# ProPrj_EIS-HW-V01_test_2026-05-23.net
KiCad netlist of a schematic drawn in EasyEDA Pro
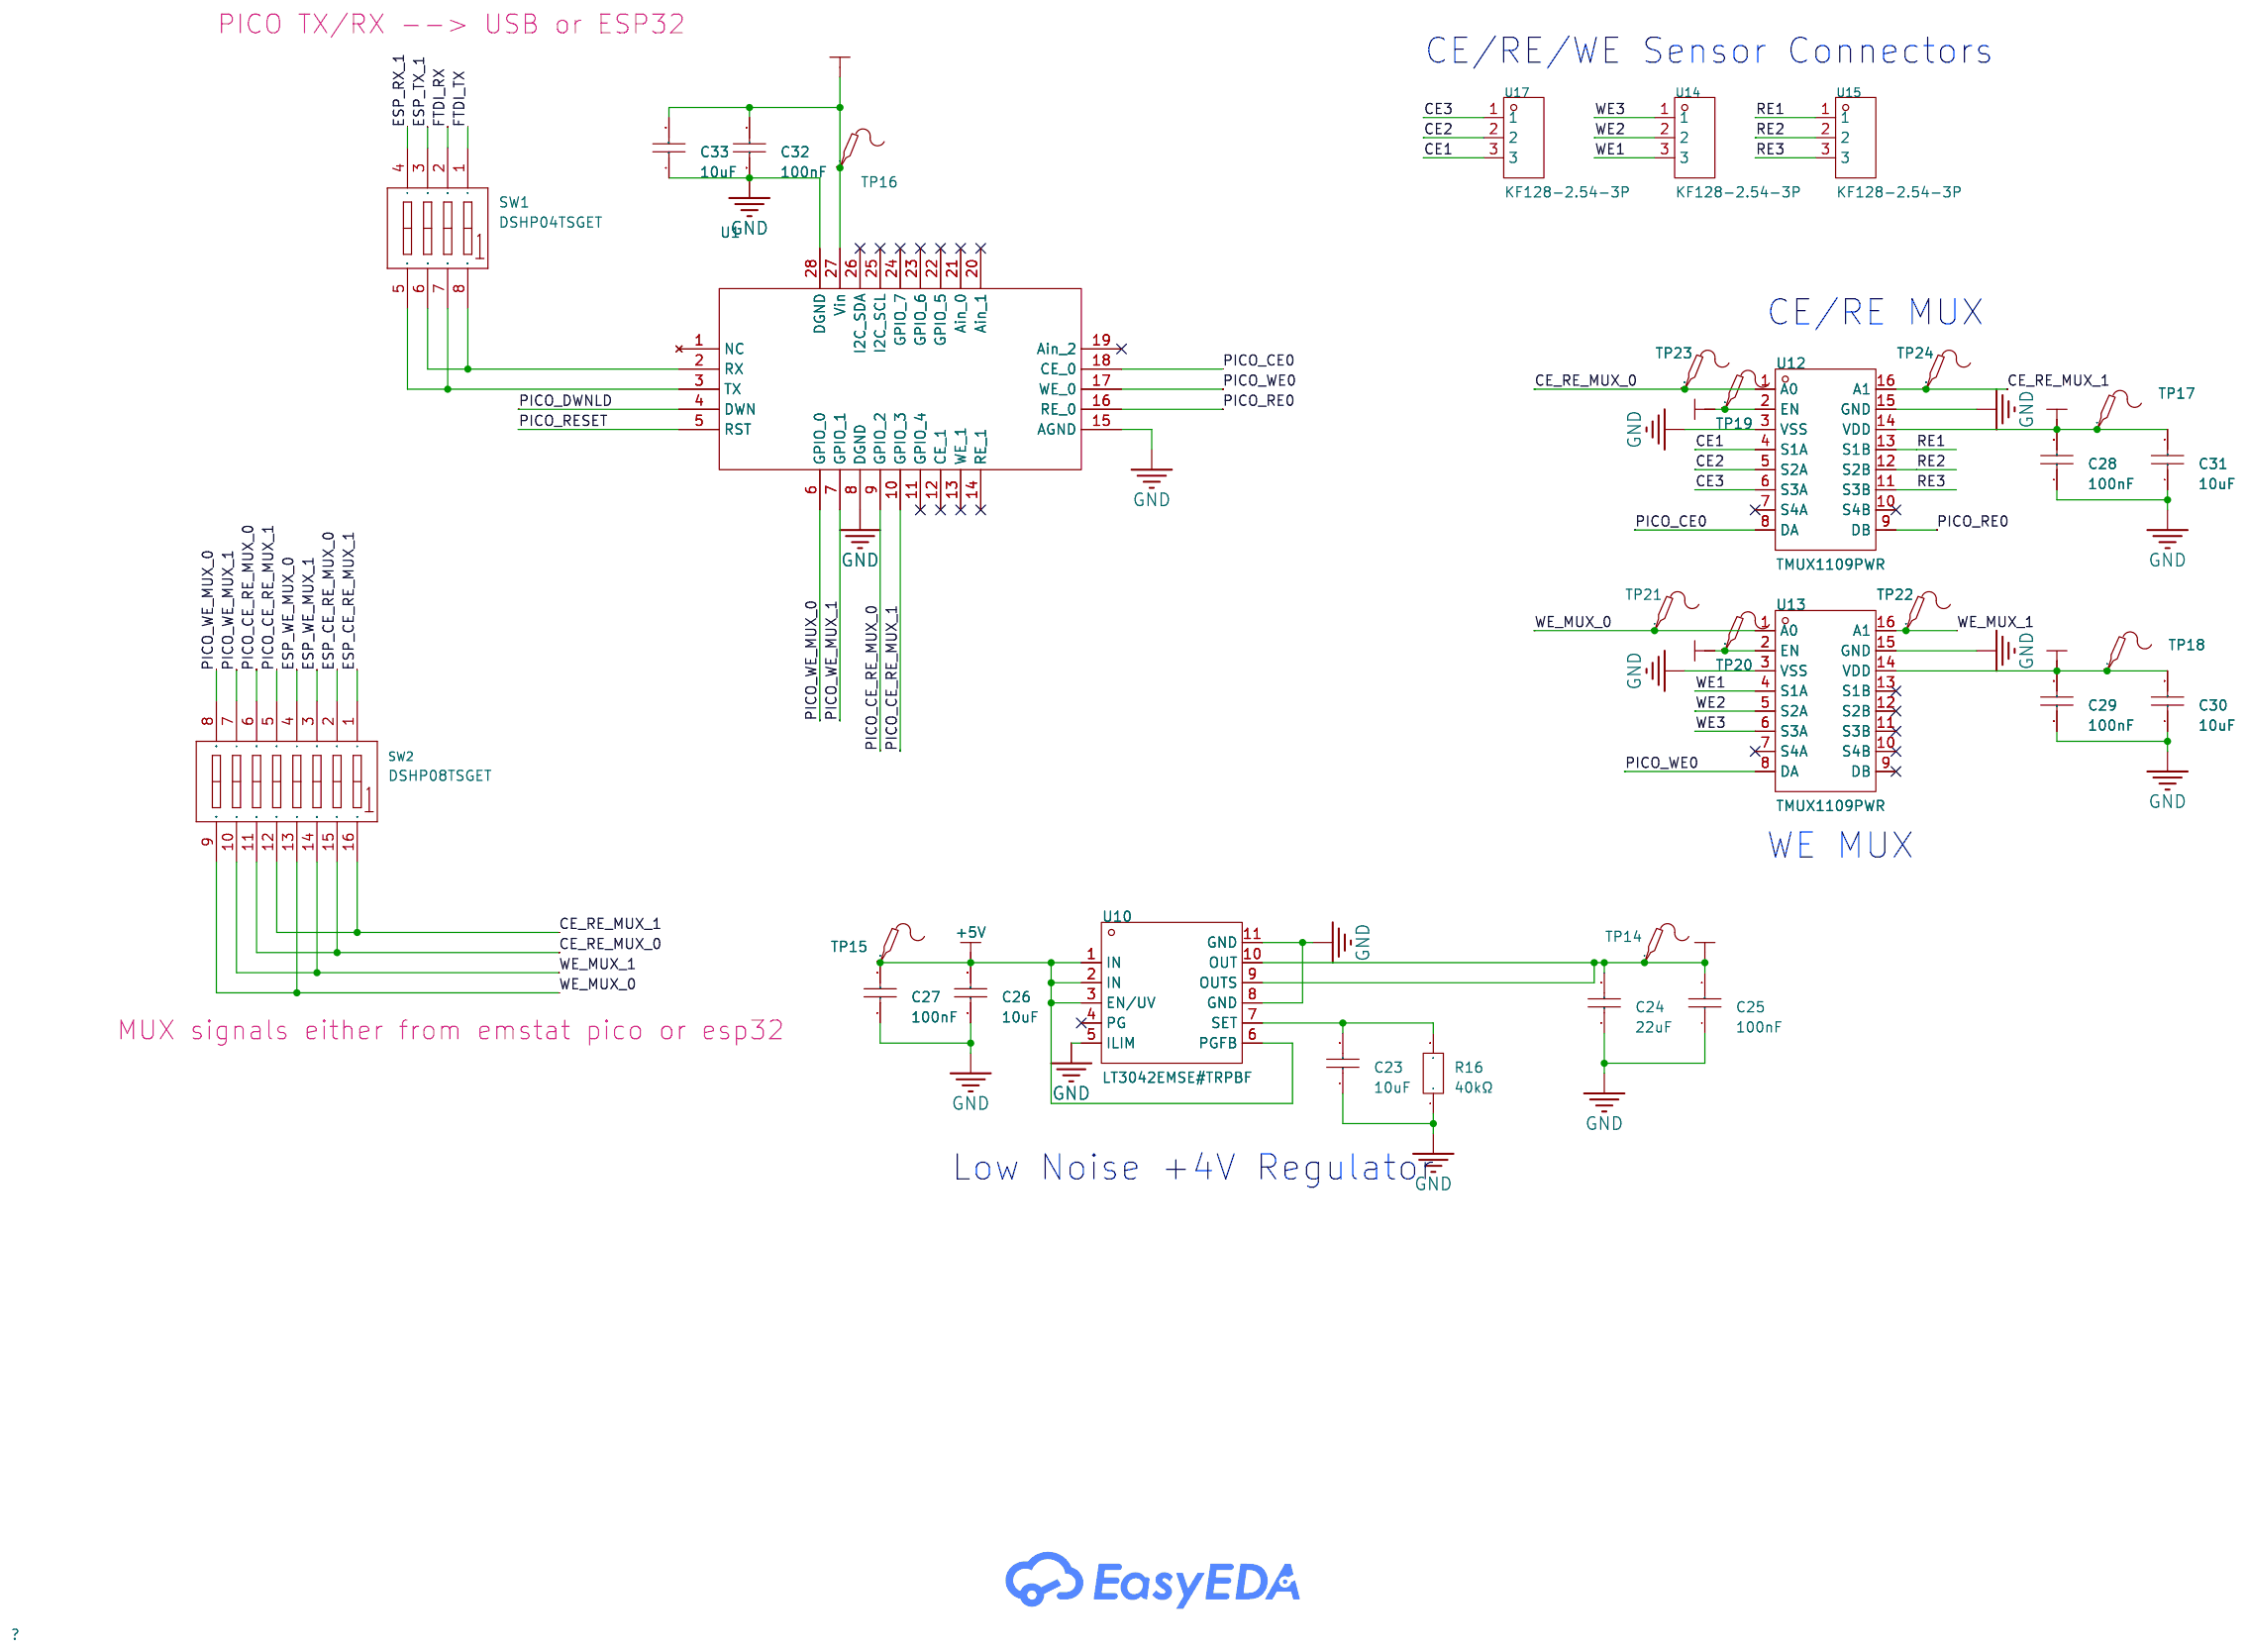
[diagram p0: P1]
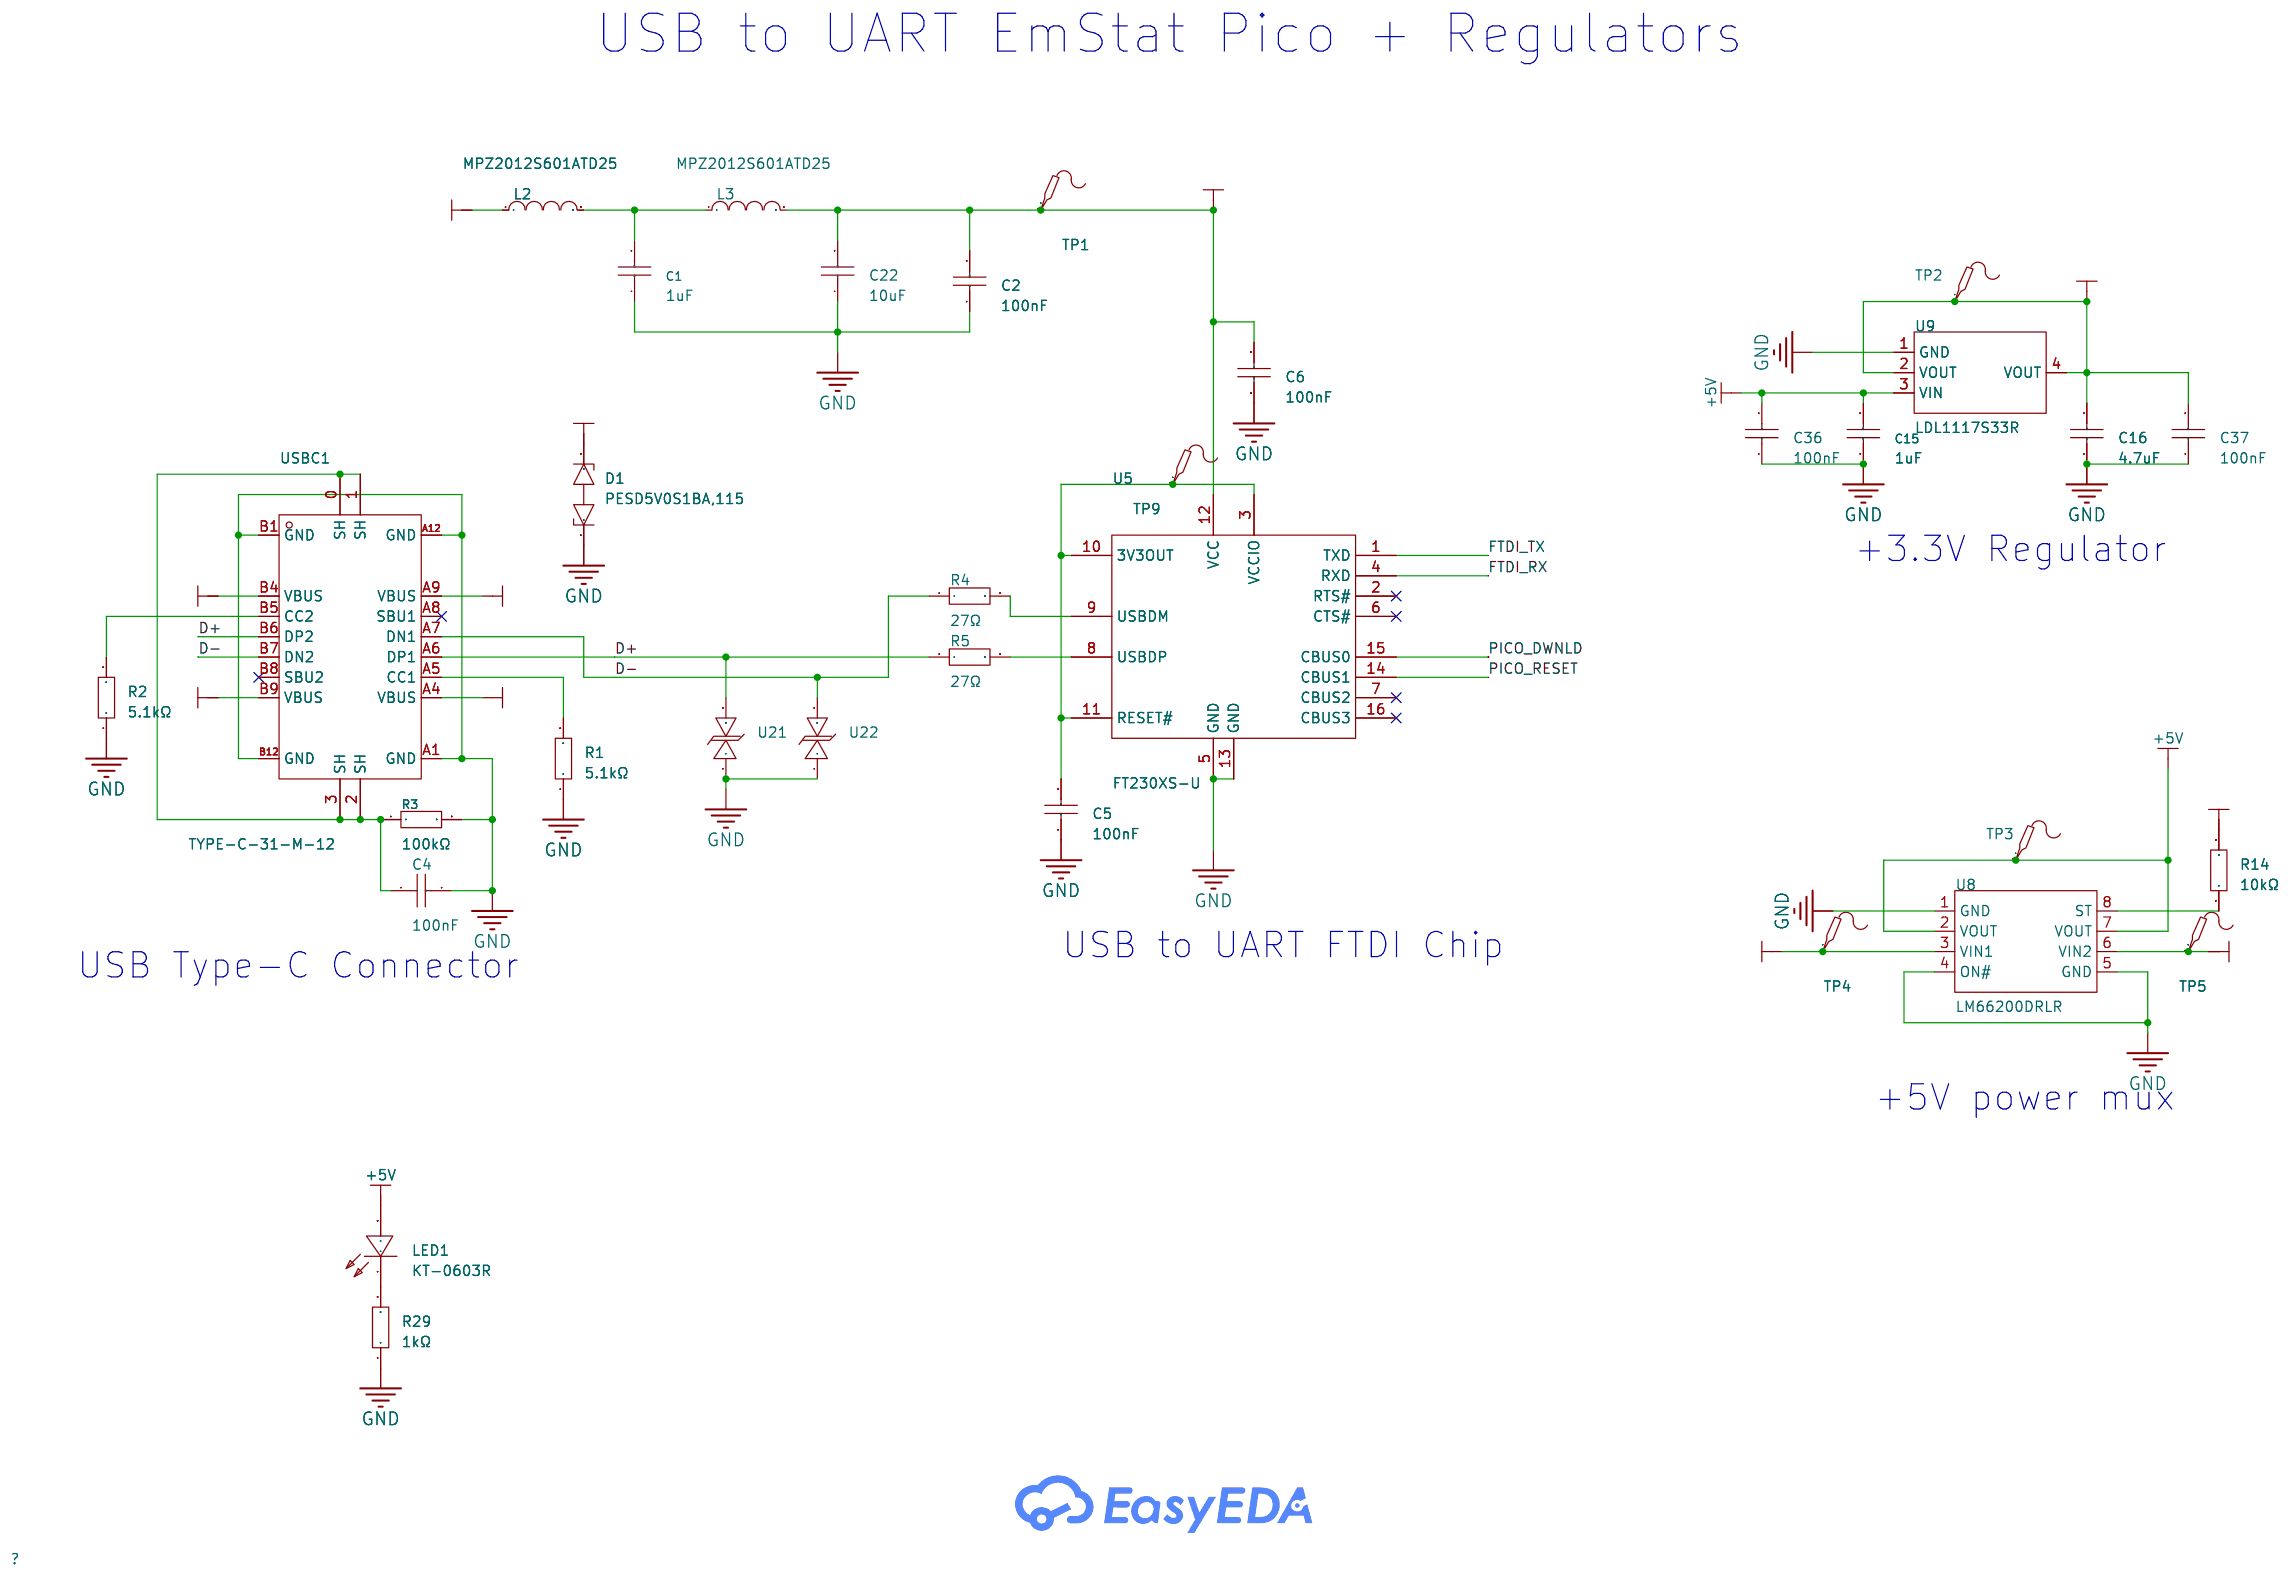
[diagram p1: P2]
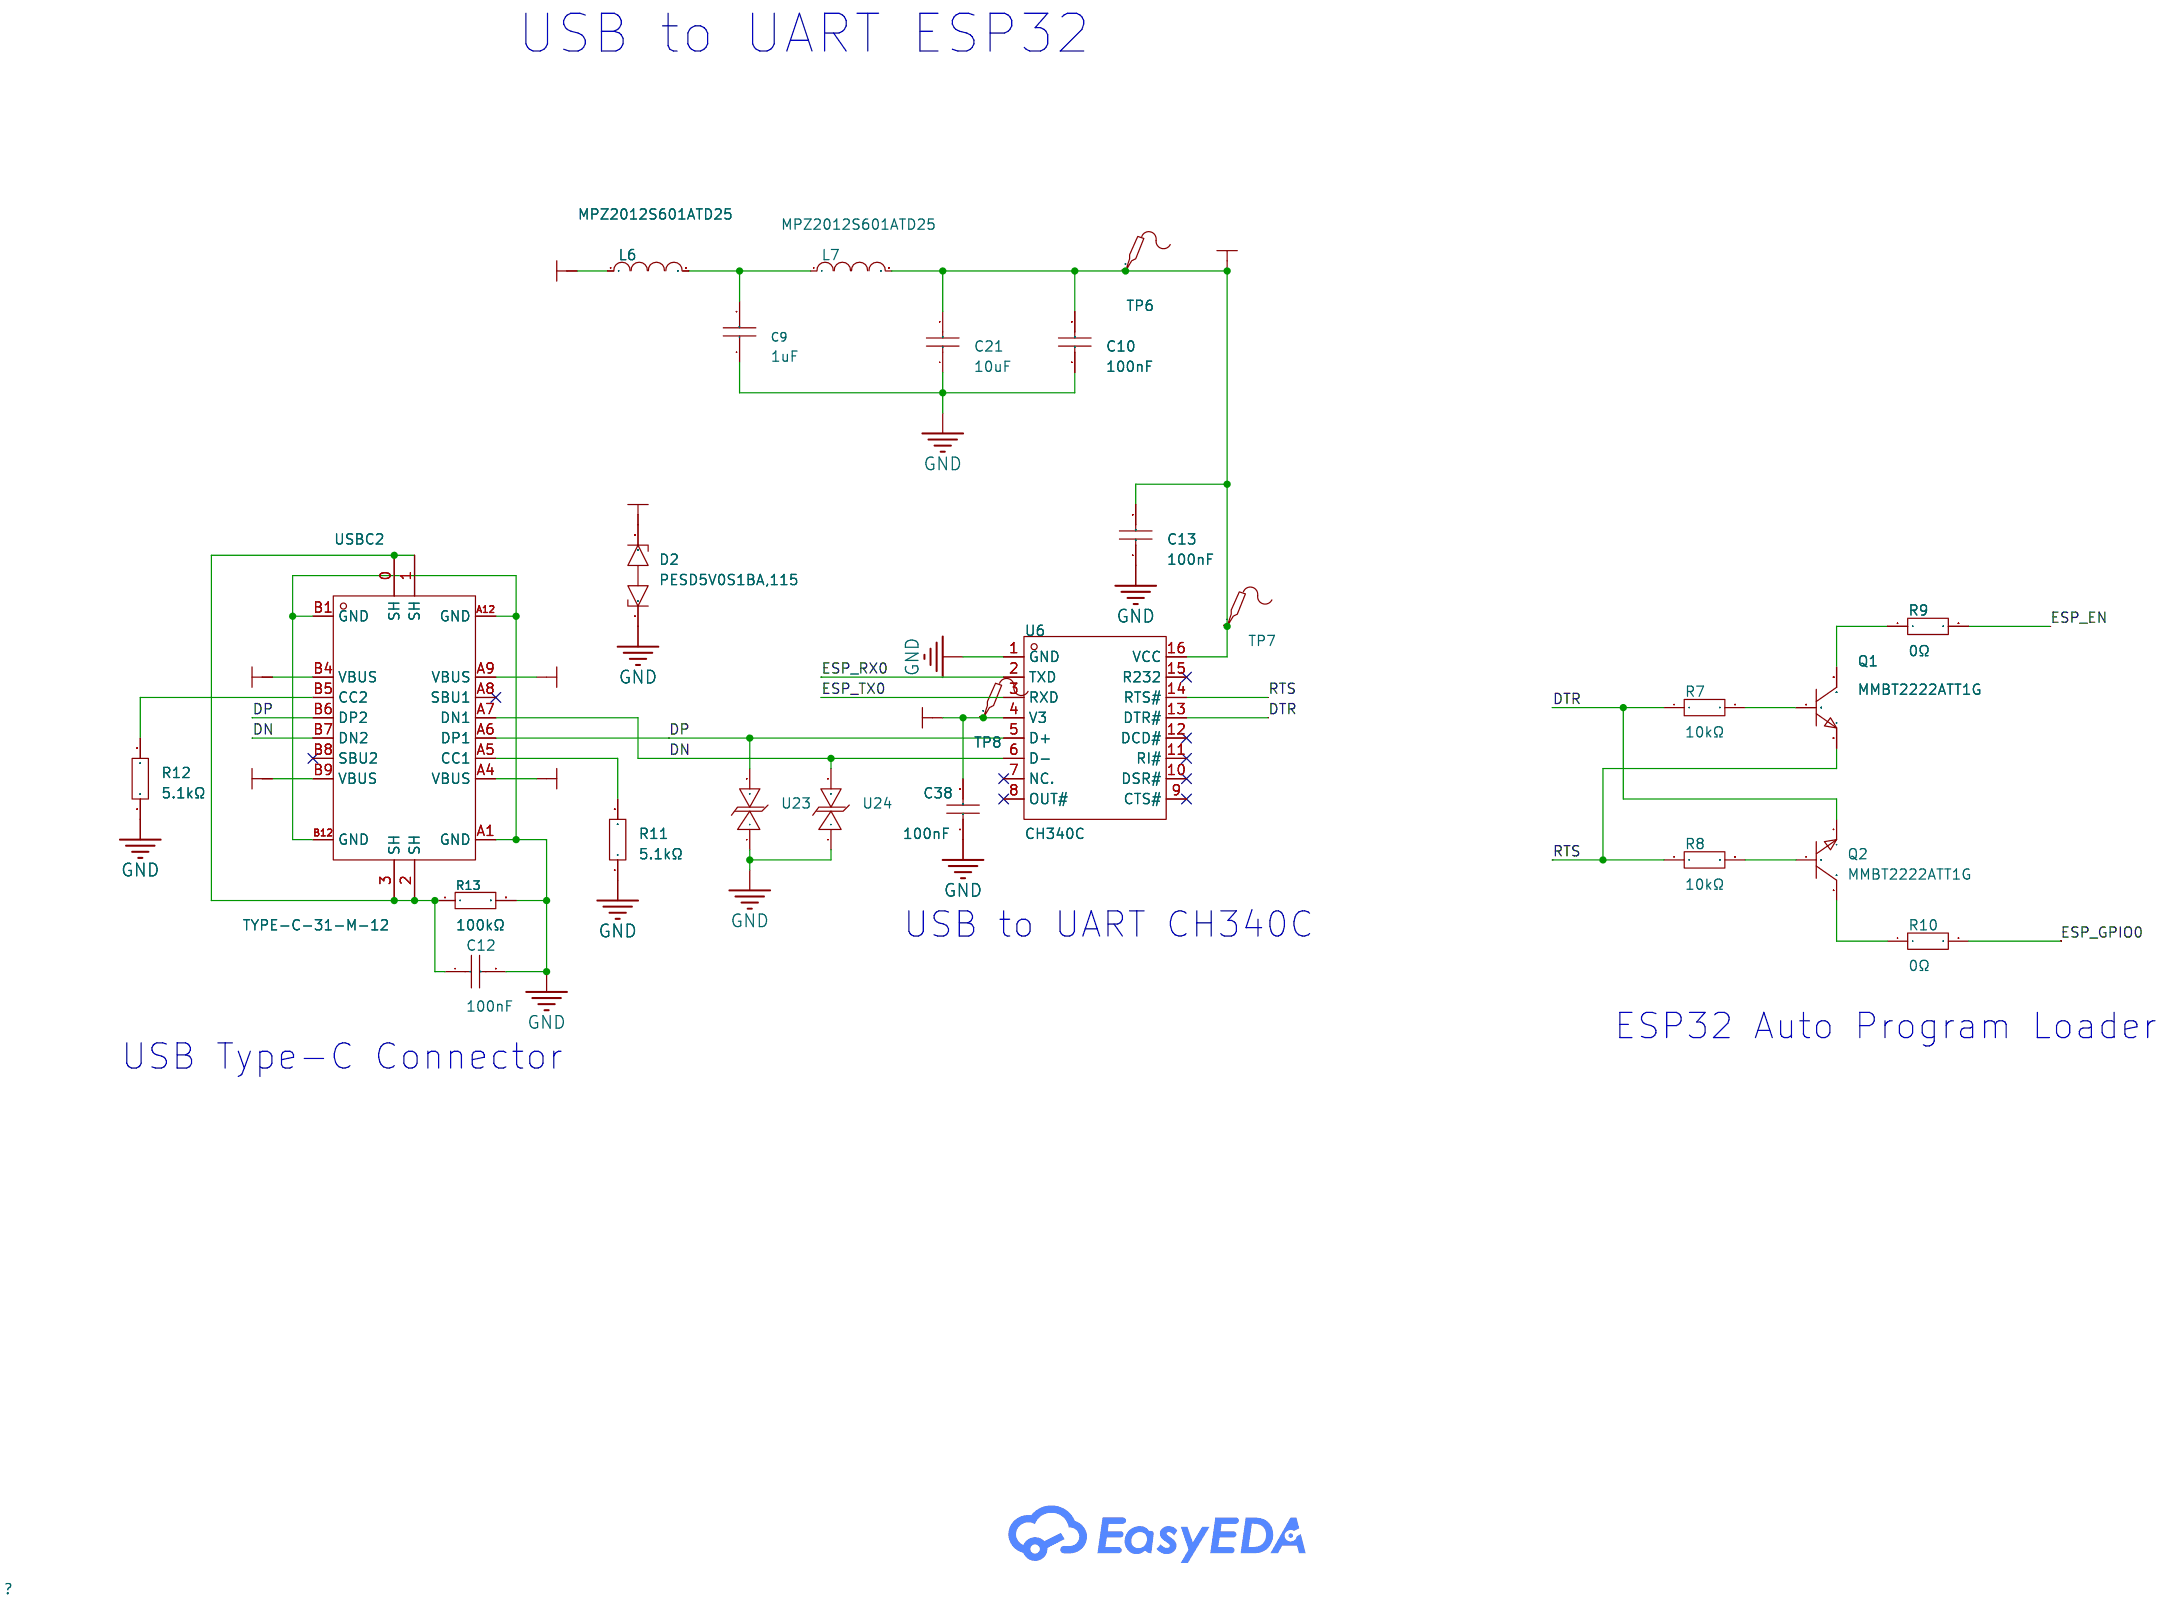
[diagram p2: P3]
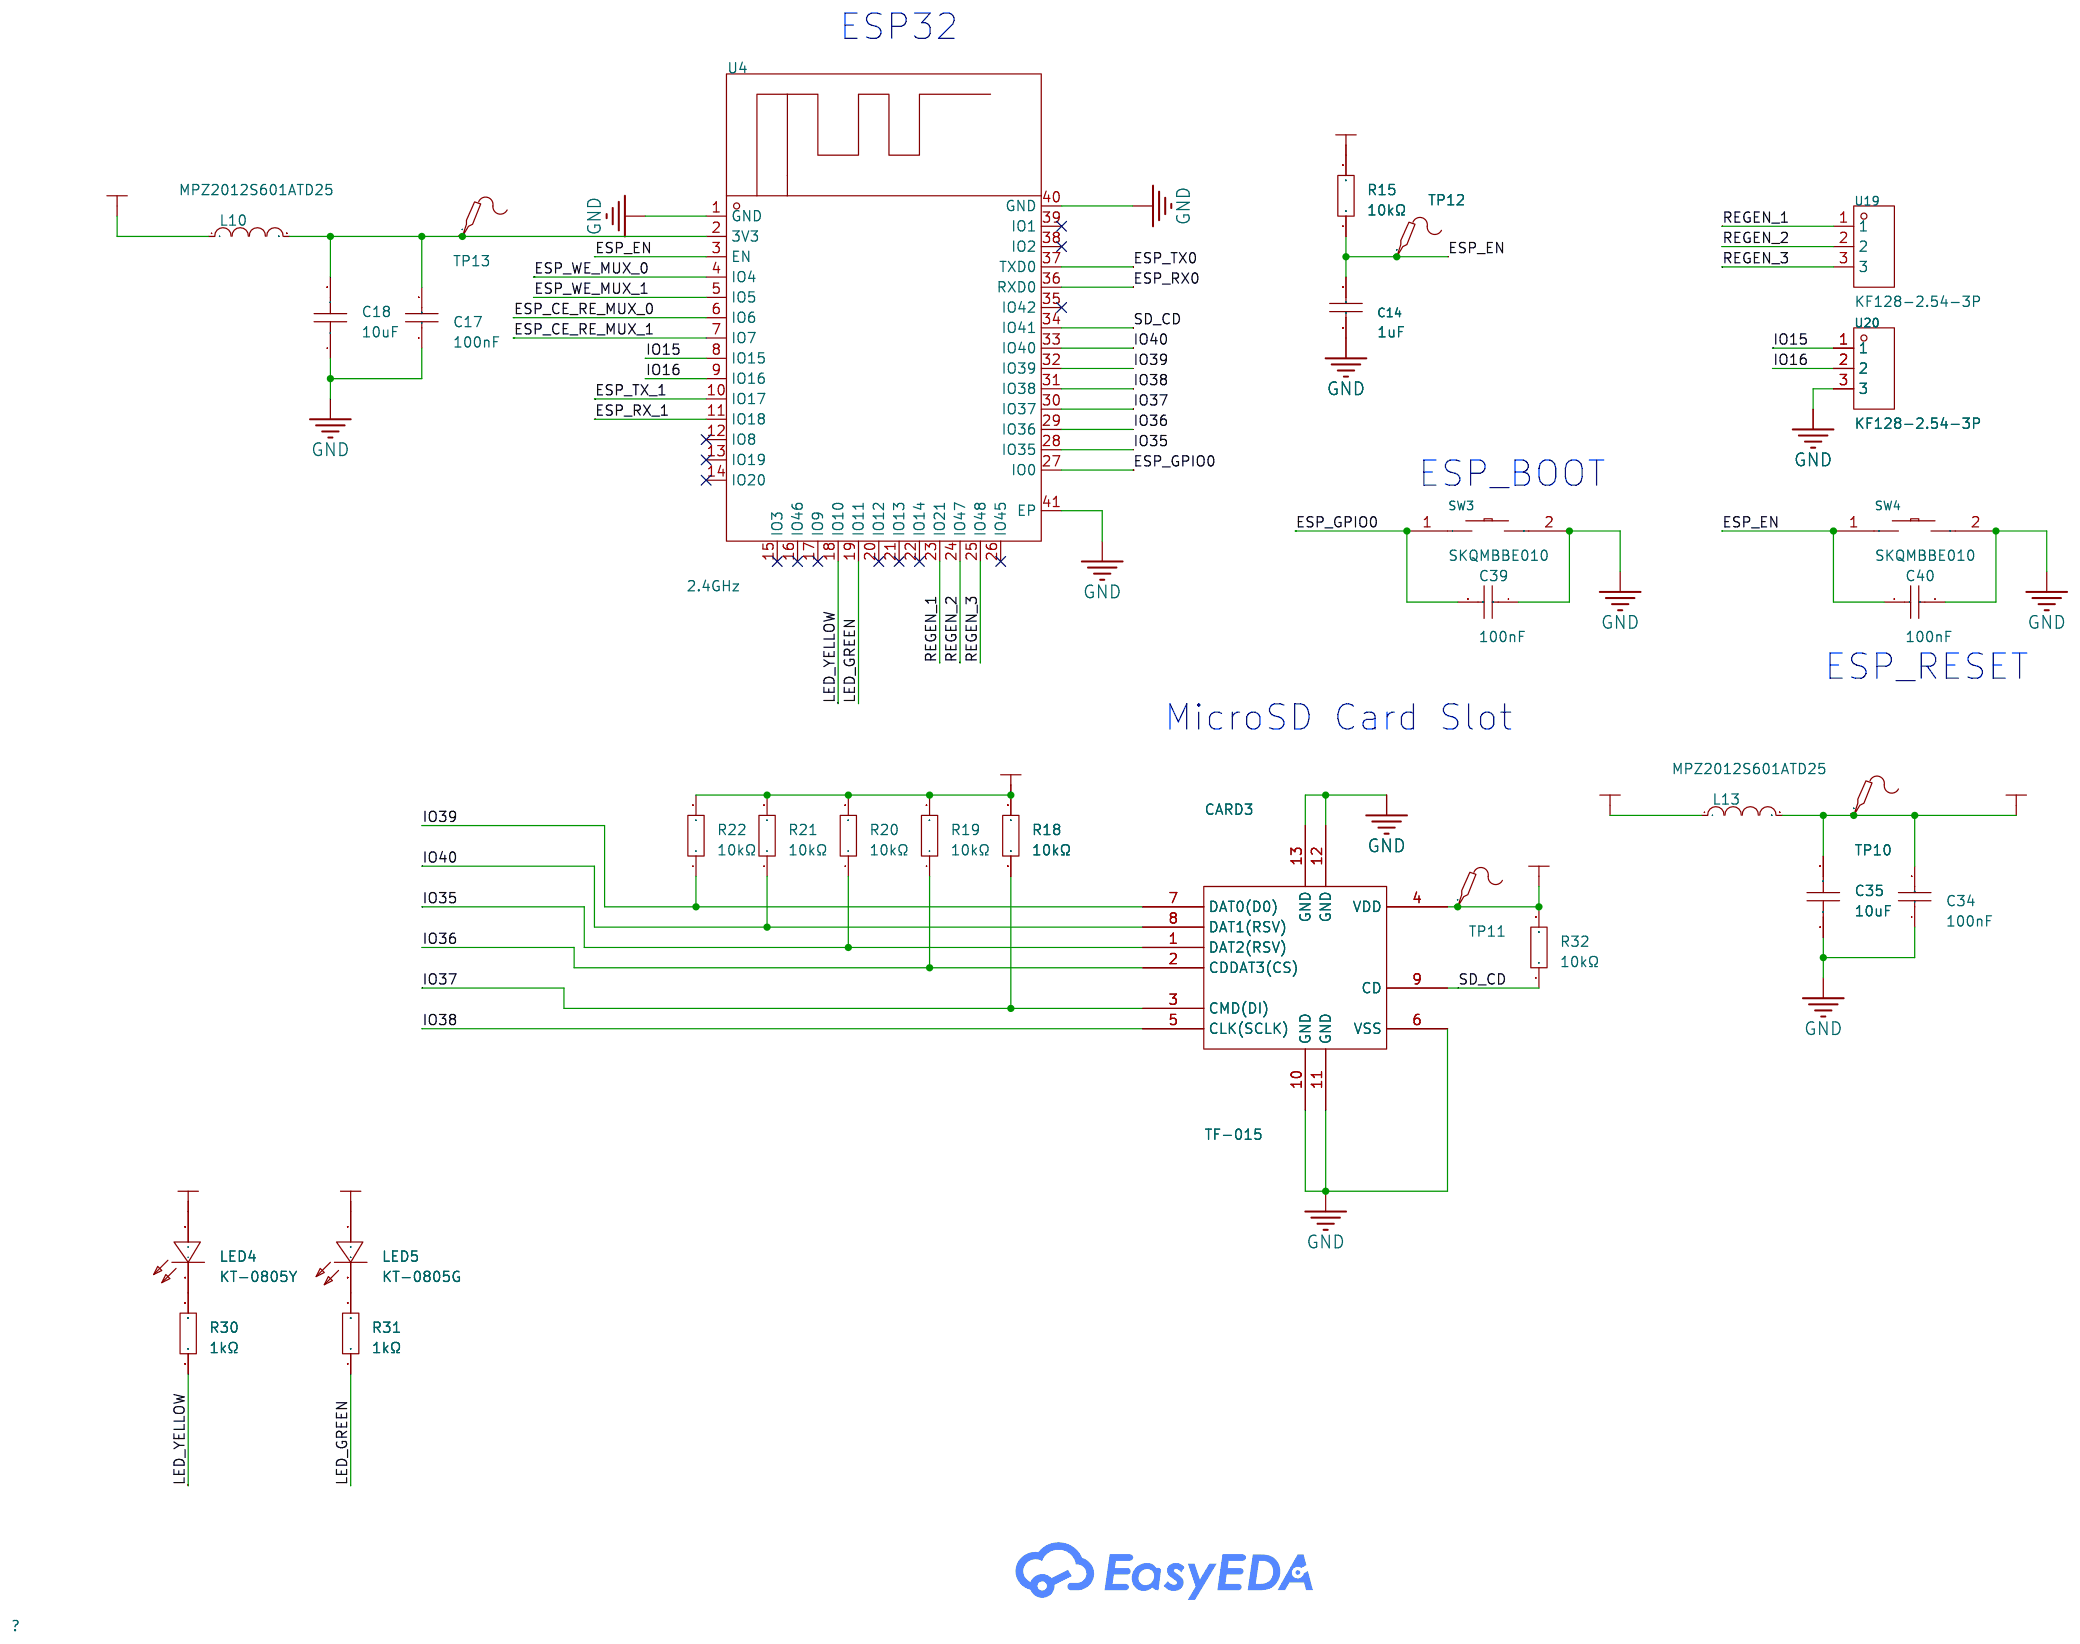
[diagram p3: P4]
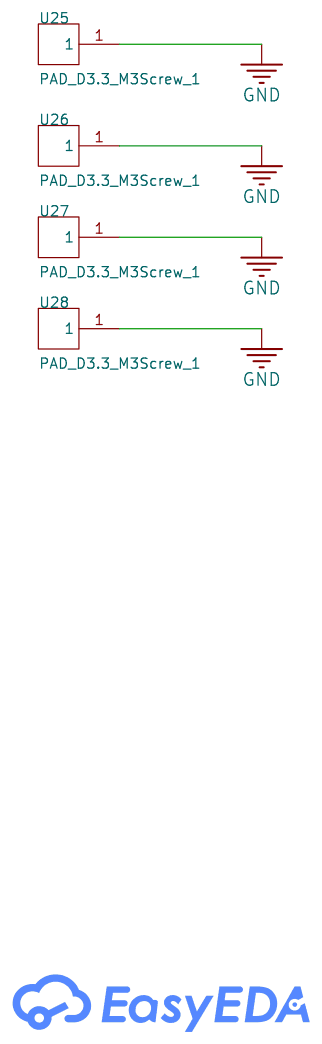
[diagram p4: P5]

(export (version "E")
  (design (tool "Eeschema 10.0.6"))
  (components
    (comp (ref "C23")
      (value "10uF")
      (footprint "easyedapro:C1206")
      (fields
        (field (name "Manufacturer Part") "CL31A106KBHNNNE")
        (field (name "Manufacturer") "SAMSUNG(三星)")
      )
      (libsource (lib "easyedapro") (part "CL31A106KBHNNNE"))
    )
    (comp (ref "C24")
      (value "22uF")
      (footprint "easyedapro:C1206")
      (fields
        (field (name "Manufacturer Part") "CL31A226KAHNNNE")
        (field (name "Manufacturer") "SAMSUNG(三星)")
      )
      (libsource (lib "easyedapro") (part "CL31A226KAHNNNE"))
    )
    (comp (ref "C25")
      (value "100nF")
      (footprint "easyedapro:C0805")
      (fields
        (field (name "Manufacturer Part") "CL21B104KCFNNNE")
        (field (name "Manufacturer") "SAMSUNG(三星)")
      )
      (libsource (lib "easyedapro") (part "CL21B104KCFNNNE"))
    )
    (comp (ref "C26")
      (value "10uF")
      (footprint "easyedapro:C1206")
      (fields
        (field (name "Manufacturer Part") "CL31A106KBHNNNE")
        (field (name "Manufacturer") "SAMSUNG(三星)")
      )
      (libsource (lib "easyedapro") (part "CL31A106KBHNNNE"))
    )
    (comp (ref "C27")
      (value "100nF")
      (footprint "easyedapro:C0805")
      (fields
        (field (name "Manufacturer Part") "CL21B104KCFNNNE")
        (field (name "Manufacturer") "SAMSUNG(三星)")
      )
      (libsource (lib "easyedapro") (part "CL21B104KCFNNNE"))
    )
    (comp (ref "C28")
      (value "100nF")
      (footprint "easyedapro:C0805")
      (fields
        (field (name "Manufacturer Part") "CL21B104KCFNNNE")
        (field (name "Manufacturer") "SAMSUNG(三星)")
      )
      (libsource (lib "easyedapro") (part "CL21B104KCFNNNE"))
    )
    (comp (ref "C29")
      (value "100nF")
      (footprint "easyedapro:C0805")
      (fields
        (field (name "Manufacturer Part") "CL21B104KCFNNNE")
        (field (name "Manufacturer") "SAMSUNG(三星)")
      )
      (libsource (lib "easyedapro") (part "CL21B104KCFNNNE"))
    )
    (comp (ref "C30")
      (value "10uF")
      (footprint "easyedapro:C1206")
      (fields
        (field (name "Manufacturer Part") "CL31A106KBHNNNE")
        (field (name "Manufacturer") "SAMSUNG(三星)")
      )
      (libsource (lib "easyedapro") (part "CL31A106KBHNNNE"))
    )
    (comp (ref "C31")
      (value "10uF")
      (footprint "easyedapro:C1206")
      (fields
        (field (name "Manufacturer Part") "CL31A106KBHNNNE")
        (field (name "Manufacturer") "SAMSUNG(三星)")
      )
      (libsource (lib "easyedapro") (part "CL31A106KBHNNNE"))
    )
    (comp (ref "C32")
      (value "100nF")
      (footprint "easyedapro:C0805")
      (fields
        (field (name "Manufacturer Part") "CL21B104KCFNNNE")
        (field (name "Manufacturer") "SAMSUNG(三星)")
      )
      (libsource (lib "easyedapro") (part "CL21B104KCFNNNE"))
    )
    (comp (ref "C33")
      (value "10uF")
      (footprint "easyedapro:C1206")
      (fields
        (field (name "Manufacturer Part") "CL31A106KBHNNNE")
        (field (name "Manufacturer") "SAMSUNG(三星)")
      )
      (libsource (lib "easyedapro") (part "CL31A106KBHNNNE"))
    )
    (comp (ref "R16")
      (value "40kΩ")
      (footprint "easyedapro:R0603")
      (fields (field (name "Manufacturer Part") "RT0603BRD0740KL") (field (name "Manufacturer") "YAGEO(国巨)"))
      (libsource (lib "easyedapro") (part "RT0603BRD0740KL"))
    )
    (comp (ref "SW1")
      (value "DSHP04TSGET")
      (footprint "easyedapro:SW-SMD_8P-L6.7-W5.4-P1.27-LS8.4")
      (description "Type:平拨,凹槽式 Circuit:SPST Number of Positions:4Bit Lead Pitch:1.27mm Operating Life:- Color:Black")
      (fields (field (name "Manufacturer") "YE"))
      (libsource (lib "easyedapro") (part "DSHP04TSGER"))
    )
    (comp (ref "SW2")
      (value "DSHP08TSGET")
      (footprint "easyedapro:SW-SMD_DSHP08TSGET")
      (description "Type:平拨,凹槽式 Circuit:SPST Number of Positions:8Bit Lead Pitch:1.27mm Operating Life:- Color:Black")
      (fields (field (name "Manufacturer") "YE"))
      (libsource (lib "easyedapro") (part "DSHP08TSGER"))
    )
    (comp (ref "TP14")
      (value "~")
      (footprint "easyedapro:Test-Point-0.5mm")
      (description "Test Point 测试点")
      (libsource (lib "easyedapro") (part "Test-Point"))
    )
    (comp (ref "TP15")
      (value "~")
      (footprint "easyedapro:Test-Point-0.5mm")
      (description "Test Point 测试点")
      (libsource (lib "easyedapro") (part "Test-Point"))
    )
    (comp (ref "TP16")
      (value "~")
      (footprint "easyedapro:Test-Point-0.5mm")
      (description "Test Point 测试点")
      (libsource (lib "easyedapro") (part "Test-Point"))
    )
    (comp (ref "TP17")
      (value "~")
      (footprint "easyedapro:Test-Point-0.5mm")
      (description "Test Point 测试点")
      (libsource (lib "easyedapro") (part "Test-Point"))
    )
    (comp (ref "TP18")
      (value "~")
      (footprint "easyedapro:Test-Point-0.5mm")
      (description "Test Point 测试点")
      (libsource (lib "easyedapro") (part "Test-Point"))
    )
    (comp (ref "TP19")
      (value "~")
      (footprint "easyedapro:Test-Point-0.5mm")
      (description "Test Point 测试点")
      (libsource (lib "easyedapro") (part "Test-Point"))
    )
    (comp (ref "TP20")
      (value "~")
      (footprint "easyedapro:Test-Point-0.5mm")
      (description "Test Point 测试点")
      (libsource (lib "easyedapro") (part "Test-Point"))
    )
    (comp (ref "TP21")
      (value "~")
      (footprint "easyedapro:Test-Point-0.5mm")
      (description "Test Point 测试点")
      (libsource (lib "easyedapro") (part "Test-Point"))
    )
    (comp (ref "TP22")
      (value "~")
      (footprint "easyedapro:Test-Point-0.5mm")
      (description "Test Point 测试点")
      (libsource (lib "easyedapro") (part "Test-Point"))
    )
    (comp (ref "TP23")
      (value "~")
      (footprint "easyedapro:Test-Point-0.5mm")
      (description "Test Point 测试点")
      (libsource (lib "easyedapro") (part "Test-Point"))
    )
    (comp (ref "TP24")
      (value "~")
      (footprint "easyedapro:Test-Point-0.5mm")
      (description "Test Point 测试点")
      (libsource (lib "easyedapro") (part "Test-Point"))
    )
    (comp (ref "U1")
      (value "EmStat Pico")
      (footprint "easyedapro:Emstat-Pico")
      (description "EmStat Pico module")
      (libsource (lib "easyedapro") (part "emstat-pico"))
    )
    (comp (ref "U10")
      (value "LT3042EMSE#TRPBF")
      (footprint "easyedapro:MSOP-10_L3.0-W3.0-P0.50-LS5.0-BL-EP")
      (fields (field (name "Manufacturer") "ADI(亚德诺)"))
      (libsource (lib "easyedapro") (part "LT3042EMSE#TRPBF"))
    )
    (comp (ref "U12")
      (value "TMUX1109PWR")
      (footprint "easyedapro:TSSOP-16_L5.0-W4.4-P0.64-LS6.4-BL")
      (fields (field (name "Manufacturer") "TI(德州仪器)"))
      (libsource (lib "easyedapro") (part "TMUX1109PWR"))
    )
    (comp (ref "U13")
      (value "TMUX1109PWR")
      (footprint "easyedapro:TSSOP-16_L5.0-W4.4-P0.64-LS6.4-BL")
      (fields (field (name "Manufacturer") "TI(德州仪器)"))
      (libsource (lib "easyedapro") (part "TMUX1109PWR"))
    )
    (comp (ref "U14")
      (value "KF128-2.54-3P")
      (footprint "easyedapro:CONN-TH_3P-P2.54_KF128-2.54-3P")
      (fields (field (name "Manufacturer") "KEFA(科发)"))
      (libsource (lib "easyedapro") (part "KF128-2.54-3P"))
    )
    (comp (ref "U15")
      (value "KF128-2.54-3P")
      (footprint "easyedapro:CONN-TH_3P-P2.54_KF128-2.54-3P")
      (fields (field (name "Manufacturer") "KEFA(科发)"))
      (libsource (lib "easyedapro") (part "KF128-2.54-3P"))
    )
    (comp (ref "U17")
      (value "KF128-2.54-3P")
      (footprint "easyedapro:CONN-TH_3P-P2.54_KF128-2.54-3P")
      (fields (field (name "Manufacturer") "KEFA(科发)"))
      (libsource (lib "easyedapro") (part "KF128-2.54-3P"))
    )
    (comp (ref "C1")
      (value "1uF")
      (footprint "easyedapro:C0805")
      (fields
        (field (name "Manufacturer Part") "CL21B105KBFNNNE")
        (field (name "Manufacturer") "SAMSUNG(三星)")
      )
      (libsource (lib "easyedapro") (part "CL21B105KBFNNNE"))
    )
    (comp (ref "C2")
      (value "100nF")
      (footprint "easyedapro:C0805")
      (fields
        (field (name "Manufacturer Part") "CL21B104KCFNNNE")
        (field (name "Manufacturer") "SAMSUNG(三星)")
      )
      (libsource (lib "easyedapro") (part "CL21B104KCFNNNE"))
    )
    (comp (ref "C4")
      (value "100nF")
      (footprint "easyedapro:C0805")
      (fields
        (field (name "Manufacturer Part") "CL21B104KCFNNNE")
        (field (name "Manufacturer") "SAMSUNG(三星)")
      )
      (libsource (lib "easyedapro") (part "CL21B104KCFNNNE"))
    )
    (comp (ref "C5")
      (value "100nF")
      (footprint "easyedapro:C0805")
      (fields
        (field (name "Manufacturer Part") "CL21B104KCFNNNE")
        (field (name "Manufacturer") "SAMSUNG(三星)")
      )
      (libsource (lib "easyedapro") (part "CL21B104KCFNNNE"))
    )
    (comp (ref "C6")
      (value "100nF")
      (footprint "easyedapro:C0805")
      (fields
        (field (name "Manufacturer Part") "CL21B104KCFNNNE")
        (field (name "Manufacturer") "SAMSUNG(三星)")
      )
      (libsource (lib "easyedapro") (part "CL21B104KCFNNNE"))
    )
    (comp (ref "C15")
      (value "1uF")
      (footprint "easyedapro:C0805")
      (fields
        (field (name "Manufacturer Part") "CL21B105KBFNNNE")
        (field (name "Manufacturer") "SAMSUNG(三星)")
      )
      (libsource (lib "easyedapro") (part "CL21B105KBFNNNE"))
    )
    (comp (ref "C16")
      (value "4.7uF")
      (footprint "easyedapro:C0805")
      (fields
        (field (name "Manufacturer Part") "CL21A475KAQNNNE")
        (field (name "Manufacturer") "SAMSUNG(三星)")
      )
      (libsource (lib "easyedapro") (part "CL21A475KAQNNNE"))
    )
    (comp (ref "C22")
      (value "10uF")
      (footprint "easyedapro:C1206")
      (fields
        (field (name "Manufacturer Part") "CL31A106KBHNNNE")
        (field (name "Manufacturer") "SAMSUNG(三星)")
      )
      (libsource (lib "easyedapro") (part "CL31A106KBHNNNE"))
    )
    (comp (ref "C36")
      (value "100nF")
      (footprint "easyedapro:C0805")
      (fields
        (field (name "Manufacturer Part") "CL21B104KCFNNNE")
        (field (name "Manufacturer") "SAMSUNG(三星)")
      )
      (libsource (lib "easyedapro") (part "CL21B104KCFNNNE"))
    )
    (comp (ref "C37")
      (value "100nF")
      (footprint "easyedapro:C0805")
      (fields
        (field (name "Manufacturer Part") "CL21B104KCFNNNE")
        (field (name "Manufacturer") "SAMSUNG(三星)")
      )
      (libsource (lib "easyedapro") (part "CL21B104KCFNNNE"))
    )
    (comp (ref "D1")
      (value "PESD5V0S1BA,115")
      (footprint "easyedapro:SOD-323_L1.7-W1.3-LS2.5-BI")
      (fields (field (name "Manufacturer") "Nexperia(安世)"))
      (libsource (lib "easyedapro") (part "PESD5V0S1BA,115"))
    )
    (comp (ref "L2")
      (value "MPZ2012S601ATD25")
      (footprint "easyedapro:L0805")
      (fields (field (name "Manufacturer") "TDK"))
      (libsource (lib "easyedapro") (part "MPZ2012S601ATD25"))
    )
    (comp (ref "L3")
      (value "MPZ2012S601ATD25")
      (footprint "easyedapro:L0805")
      (fields (field (name "Manufacturer") "TDK"))
      (libsource (lib "easyedapro") (part "MPZ2012S601ATD25"))
    )
    (comp (ref "LED1")
      (value "KT-0603R")
      (footprint "easyedapro:LED0603-RD")
      (fields (field (name "Manufacturer") "KENTO"))
      (libsource (lib "easyedapro") (part "KT-0603R"))
    )
    (comp (ref "R1")
      (value "5.1kΩ")
      (footprint "easyedapro:R0805")
      (fields
        (field (name "Manufacturer Part") "0805W8F5101T5E")
        (field (name "Manufacturer") "UNI-ROYAL(厚声)")
      )
      (libsource (lib "easyedapro") (part "0805W8F5101T5E"))
    )
    (comp (ref "R2")
      (value "5.1kΩ")
      (footprint "easyedapro:R0805")
      (fields
        (field (name "Manufacturer Part") "0805W8F5101T5E")
        (field (name "Manufacturer") "UNI-ROYAL(厚声)")
      )
      (libsource (lib "easyedapro") (part "0805W8F5101T5E"))
    )
    (comp (ref "R3")
      (value "100kΩ")
      (footprint "easyedapro:R0805")
      (fields
        (field (name "Manufacturer Part") "0805W8F1003T5E")
        (field (name "Manufacturer") "UNI-ROYAL(厚声)")
      )
      (libsource (lib "easyedapro") (part "0805W8F1003T5E_C149504"))
    )
    (comp (ref "R4")
      (value "27Ω")
      (footprint "easyedapro:R0805")
      (fields
        (field (name "Manufacturer Part") "0805W8F270JT5E")
        (field (name "Manufacturer") "UNI-ROYAL(厚声)")
      )
      (libsource (lib "easyedapro") (part "0805W8F270JT5E"))
    )
    (comp (ref "R5")
      (value "27Ω")
      (footprint "easyedapro:R0805")
      (fields
        (field (name "Manufacturer Part") "0805W8F270JT5E")
        (field (name "Manufacturer") "UNI-ROYAL(厚声)")
      )
      (libsource (lib "easyedapro") (part "0805W8F270JT5E"))
    )
    (comp (ref "R14")
      (value "10kΩ")
      (footprint "easyedapro:R0805")
      (fields
        (field (name "Manufacturer Part") "0805W8F1002T5E")
        (field (name "Manufacturer") "UNI-ROYAL(厚声)")
      )
      (libsource (lib "easyedapro") (part "0805W8F1002T5E"))
    )
    (comp (ref "R29")
      (value "1kΩ")
      (footprint "easyedapro:R0603")
      (fields
        (field (name "Manufacturer Part") "0603WAF1001T5E")
        (field (name "Manufacturer") "UNI-ROYAL(厚声)")
      )
      (libsource (lib "easyedapro") (part "0603WAF1001T5E"))
    )
    (comp (ref "TP1")
      (value "~")
      (footprint "easyedapro:Test-Point-0.5mm")
      (description "Test Point 测试点")
      (libsource (lib "easyedapro") (part "Test-Point"))
    )
    (comp (ref "TP2")
      (value "~")
      (footprint "easyedapro:Test-Point-0.5mm")
      (description "Test Point 测试点")
      (libsource (lib "easyedapro") (part "Test-Point"))
    )
    (comp (ref "TP3")
      (value "~")
      (footprint "easyedapro:Test-Point-0.5mm")
      (description "Test Point 测试点")
      (libsource (lib "easyedapro") (part "Test-Point"))
    )
    (comp (ref "TP4")
      (value "~")
      (footprint "easyedapro:Test-Point-0.5mm")
      (description "Test Point 测试点")
      (libsource (lib "easyedapro") (part "Test-Point"))
    )
    (comp (ref "TP5")
      (value "~")
      (footprint "easyedapro:Test-Point-0.5mm")
      (description "Test Point 测试点")
      (libsource (lib "easyedapro") (part "Test-Point"))
    )
    (comp (ref "TP9")
      (value "~")
      (footprint "easyedapro:Test-Point-0.5mm")
      (description "Test Point 测试点")
      (libsource (lib "easyedapro") (part "Test-Point"))
    )
    (comp (ref "U5")
      (value "FT230XS-U")
      (footprint "easyedapro:SSOP-16_L5.0-W4.4-P0.65-LS6.4-BL")
      (fields (field (name "Manufacturer") "FTDI(飞特帝亚)"))
      (libsource (lib "easyedapro") (part "FT230XS-U"))
    )
    (comp (ref "U8")
      (value "LM66200DRLR")
      (footprint "easyedapro:SOT-583-8_L2.1-W1.2-P0.50-LS1.6-BL")
      (fields (field (name "Manufacturer") "TI(德州仪器)"))
      (libsource (lib "easyedapro") (part "LM66200DRLR"))
    )
    (comp (ref "U9")
      (value "LDL1117S33R")
      (footprint "easyedapro:SOT-223-4_L6.5-W3.5-P2.30-LS7.0-BR")
      (fields (field (name "Manufacturer") "ST(意法半导体)"))
      (libsource (lib "easyedapro") (part "LDL1117S33R"))
    )
    (comp (ref "U21")
      (value "BNLESD5D5.0CT1G")
      (footprint "easyedapro:SOD-523_L1.2-W0.8-LS1.6-BI")
      (fields (field (name "Manufacturer") "BORN(伯恩半导体)"))
      (libsource (lib "easyedapro") (part "BNLESD5D5.0CT1G"))
    )
    (comp (ref "U22")
      (value "BNLESD5D5.0CT1G")
      (footprint "easyedapro:SOD-523_L1.2-W0.8-LS1.6-BI")
      (fields (field (name "Manufacturer") "BORN(伯恩半导体)"))
      (libsource (lib "easyedapro") (part "BNLESD5D5.0CT1G"))
    )
    (comp (ref "USBC1")
      (value "TYPE-C-31-M-12")
      (footprint "easyedapro:USB-C_SMD-TYPE-C-31-M-12")
      (fields (field (name "Manufacturer") "韩国韩荣"))
      (libsource (lib "easyedapro") (part "TYPE-C-31-M-12"))
    )
    (comp (ref "C9")
      (value "1uF")
      (footprint "easyedapro:C0805")
      (fields
        (field (name "Manufacturer Part") "CL21B105KBFNNNE")
        (field (name "Manufacturer") "SAMSUNG(三星)")
      )
      (libsource (lib "easyedapro") (part "CL21B105KBFNNNE"))
    )
    (comp (ref "C10")
      (value "100nF")
      (footprint "easyedapro:C0805")
      (fields
        (field (name "Manufacturer Part") "CL21B104KCFNNNE")
        (field (name "Manufacturer") "SAMSUNG(三星)")
      )
      (libsource (lib "easyedapro") (part "CL21B104KCFNNNE"))
    )
    (comp (ref "C12")
      (value "100nF")
      (footprint "easyedapro:C0805")
      (fields
        (field (name "Manufacturer Part") "CL21B104KCFNNNE")
        (field (name "Manufacturer") "SAMSUNG(三星)")
      )
      (libsource (lib "easyedapro") (part "CL21B104KCFNNNE"))
    )
    (comp (ref "C13")
      (value "100nF")
      (footprint "easyedapro:C0805")
      (fields
        (field (name "Manufacturer Part") "CL21B104KCFNNNE")
        (field (name "Manufacturer") "SAMSUNG(三星)")
      )
      (libsource (lib "easyedapro") (part "CL21B104KCFNNNE"))
    )
    (comp (ref "C21")
      (value "10uF")
      (footprint "easyedapro:C1206")
      (fields
        (field (name "Manufacturer Part") "CL31A106KBHNNNE")
        (field (name "Manufacturer") "SAMSUNG(三星)")
      )
      (libsource (lib "easyedapro") (part "CL31A106KBHNNNE"))
    )
    (comp (ref "C38")
      (value "100nF")
      (footprint "easyedapro:C0805")
      (fields
        (field (name "Manufacturer Part") "CL21B104KCFNNNE")
        (field (name "Manufacturer") "SAMSUNG(三星)")
      )
      (libsource (lib "easyedapro") (part "CL21B104KCFNNNE"))
    )
    (comp (ref "D2")
      (value "PESD5V0S1BA,115")
      (footprint "easyedapro:SOD-323_L1.7-W1.3-LS2.5-BI")
      (fields (field (name "Manufacturer") "Nexperia(安世)"))
      (libsource (lib "easyedapro") (part "PESD5V0S1BA,115"))
    )
    (comp (ref "L6")
      (value "MPZ2012S601ATD25")
      (footprint "easyedapro:L0805")
      (fields (field (name "Manufacturer") "TDK"))
      (libsource (lib "easyedapro") (part "MPZ2012S601ATD25"))
    )
    (comp (ref "L7")
      (value "MPZ2012S601ATD25")
      (footprint "easyedapro:L0805")
      (fields (field (name "Manufacturer") "TDK"))
      (libsource (lib "easyedapro") (part "MPZ2012S601ATD25"))
    )
    (comp (ref "Q1")
      (value "MMBT2222ATT1G")
      (footprint "easyedapro:SC-75-3_L1.6-W0.8-P1.00-LS1.6-BR")
      (fields (field (name "Manufacturer") "onsemi(安森美)"))
      (libsource (lib "easyedapro") (part "MMBT2222ATT1G"))
    )
    (comp (ref "Q2")
      (value "MMBT2222ATT1G")
      (footprint "easyedapro:SC-75-3_L1.6-W0.8-P1.00-LS1.6-BR")
      (fields (field (name "Manufacturer") "onsemi(安森美)"))
      (libsource (lib "easyedapro") (part "MMBT2222ATT1G"))
    )
    (comp (ref "R7")
      (value "10kΩ")
      (footprint "easyedapro:R0805")
      (fields
        (field (name "Manufacturer Part") "0805W8F1002T5E")
        (field (name "Manufacturer") "UNI-ROYAL(厚声)")
      )
      (libsource (lib "easyedapro") (part "0805W8F1002T5E"))
    )
    (comp (ref "R8")
      (value "10kΩ")
      (footprint "easyedapro:R0805")
      (fields
        (field (name "Manufacturer Part") "0805W8F1002T5E")
        (field (name "Manufacturer") "UNI-ROYAL(厚声)")
      )
      (libsource (lib "easyedapro") (part "0805W8F1002T5E"))
    )
    (comp (ref "R9")
      (value "0Ω")
      (footprint "easyedapro:R0805")
      (fields
        (field (name "Manufacturer Part") "0805W8F0000T5E")
        (field (name "Manufacturer") "UNI-ROYAL(厚声)")
      )
      (libsource (lib "easyedapro") (part "0805W8F0000T5E"))
    )
    (comp (ref "R10")
      (value "0Ω")
      (footprint "easyedapro:R0805")
      (fields
        (field (name "Manufacturer Part") "0805W8F0000T5E")
        (field (name "Manufacturer") "UNI-ROYAL(厚声)")
      )
      (libsource (lib "easyedapro") (part "0805W8F0000T5E"))
    )
    (comp (ref "R11")
      (value "5.1kΩ")
      (footprint "easyedapro:R0805")
      (fields
        (field (name "Manufacturer Part") "0805W8F5101T5E")
        (field (name "Manufacturer") "UNI-ROYAL(厚声)")
      )
      (libsource (lib "easyedapro") (part "0805W8F5101T5E"))
    )
    (comp (ref "R12")
      (value "5.1kΩ")
      (footprint "easyedapro:R0805")
      (fields
        (field (name "Manufacturer Part") "0805W8F5101T5E")
        (field (name "Manufacturer") "UNI-ROYAL(厚声)")
      )
      (libsource (lib "easyedapro") (part "0805W8F5101T5E"))
    )
    (comp (ref "R13")
      (value "100kΩ")
      (footprint "easyedapro:R0805")
      (fields
        (field (name "Manufacturer Part") "0805W8F1003T5E")
        (field (name "Manufacturer") "UNI-ROYAL(厚声)")
      )
      (libsource (lib "easyedapro") (part "0805W8F1003T5E_C149504"))
    )
    (comp (ref "TP6")
      (value "~")
      (footprint "easyedapro:Test-Point-0.5mm")
      (description "Test Point 测试点")
      (libsource (lib "easyedapro") (part "Test-Point"))
    )
    (comp (ref "TP7")
      (value "~")
      (footprint "easyedapro:Test-Point-0.5mm")
      (description "Test Point 测试点")
      (libsource (lib "easyedapro") (part "Test-Point"))
    )
    (comp (ref "TP8")
      (value "~")
      (footprint "easyedapro:Test-Point-0.5mm")
      (description "Test Point 测试点")
      (libsource (lib "easyedapro") (part "Test-Point"))
    )
    (comp (ref "U6")
      (value "CH340C")
      (footprint "easyedapro:SOP-16_L10.0-W3.9-P1.27-LS6.0-BL")
      (fields (field (name "Manufacturer") "WCH(南京沁恒)"))
      (libsource (lib "easyedapro") (part "CH340C"))
    )
    (comp (ref "U23")
      (value "BNLESD5D5.0CT1G")
      (footprint "easyedapro:SOD-523_L1.2-W0.8-LS1.6-BI")
      (fields (field (name "Manufacturer") "BORN(伯恩半导体)"))
      (libsource (lib "easyedapro") (part "BNLESD5D5.0CT1G"))
    )
    (comp (ref "U24")
      (value "BNLESD5D5.0CT1G")
      (footprint "easyedapro:SOD-523_L1.2-W0.8-LS1.6-BI")
      (fields (field (name "Manufacturer") "BORN(伯恩半导体)"))
      (libsource (lib "easyedapro") (part "BNLESD5D5.0CT1G"))
    )
    (comp (ref "USBC2")
      (value "TYPE-C-31-M-12")
      (footprint "easyedapro:USB-C_SMD-TYPE-C-31-M-12")
      (fields (field (name "Manufacturer") "韩国韩荣"))
      (libsource (lib "easyedapro") (part "TYPE-C-31-M-12"))
    )
    (comp (ref "C14")
      (value "1uF")
      (footprint "easyedapro:C0805")
      (fields
        (field (name "Manufacturer Part") "CL21B105KBFNNNE")
        (field (name "Manufacturer") "SAMSUNG(三星)")
      )
      (libsource (lib "easyedapro") (part "CL21B105KBFNNNE"))
    )
    (comp (ref "C17")
      (value "100nF")
      (footprint "easyedapro:C0805")
      (fields
        (field (name "Manufacturer Part") "CL21B104KCFNNNE")
        (field (name "Manufacturer") "SAMSUNG(三星)")
      )
      (libsource (lib "easyedapro") (part "CL21B104KCFNNNE"))
    )
    (comp (ref "C18")
      (value "10uF")
      (footprint "easyedapro:C0805")
      (fields
        (field (name "Manufacturer Part") "CL21A106KAYNNNE")
        (field (name "Manufacturer") "SAMSUNG(三星)")
      )
      (libsource (lib "easyedapro") (part "CL21A106KAYNNNE"))
    )
    (comp (ref "C34")
      (value "100nF")
      (footprint "easyedapro:C0805")
      (fields
        (field (name "Manufacturer Part") "CL21B104KCFNNNE")
        (field (name "Manufacturer") "SAMSUNG(三星)")
      )
      (libsource (lib "easyedapro") (part "CL21B104KCFNNNE"))
    )
    (comp (ref "C35")
      (value "10uF")
      (footprint "easyedapro:C0805")
      (fields
        (field (name "Manufacturer Part") "CL21A106KAYNNNE")
        (field (name "Manufacturer") "SAMSUNG(三星)")
      )
      (libsource (lib "easyedapro") (part "CL21A106KAYNNNE"))
    )
    (comp (ref "C39")
      (value "100nF")
      (footprint "easyedapro:C0805")
      (fields
        (field (name "Manufacturer Part") "CL21B104KCFNNNE")
        (field (name "Manufacturer") "SAMSUNG(三星)")
      )
      (libsource (lib "easyedapro") (part "CL21B104KCFNNNE"))
    )
    (comp (ref "C40")
      (value "100nF")
      (footprint "easyedapro:C0805")
      (fields
        (field (name "Manufacturer Part") "CL21B104KCFNNNE")
        (field (name "Manufacturer") "SAMSUNG(三星)")
      )
      (libsource (lib "easyedapro") (part "CL21B104KCFNNNE"))
    )
    (comp (ref "CARD3")
      (value "TF-015")
      (footprint "easyedapro:TF-SMD_TF-015")
      (fields (field (name "Manufacturer") "SOFNG(硕方)"))
      (libsource (lib "easyedapro") (part "TF-015"))
    )
    (comp (ref "L10")
      (value "MPZ2012S601ATD25")
      (footprint "easyedapro:L0805")
      (fields (field (name "Manufacturer") "TDK"))
      (libsource (lib "easyedapro") (part "MPZ2012S601ATD25"))
    )
    (comp (ref "L13")
      (value "MPZ2012S601ATD25")
      (footprint "easyedapro:L0805")
      (fields (field (name "Manufacturer") "TDK"))
      (libsource (lib "easyedapro") (part "MPZ2012S601ATD25"))
    )
    (comp (ref "LED4")
      (value "KT-0805Y")
      (footprint "easyedapro:LED0805-R-RD")
      (fields (field (name "Manufacturer") "KENTO"))
      (libsource (lib "easyedapro") (part "17-21SUYC/TR8"))
    )
    (comp (ref "LED5")
      (value "KT-0805G")
      (footprint "easyedapro:LED0805-R-RD")
      (fields (field (name "Manufacturer") "KENTO"))
      (libsource (lib "easyedapro") (part "0805G (Green)"))
    )
    (comp (ref "R15")
      (value "10kΩ")
      (footprint "easyedapro:R0805")
      (fields
        (field (name "Manufacturer Part") "0805W8F1002T5E")
        (field (name "Manufacturer") "UNI-ROYAL(厚声)")
      )
      (libsource (lib "easyedapro") (part "0805W8F1002T5E"))
    )
    (comp (ref "R18")
      (value "10kΩ")
      (footprint "easyedapro:R0805")
      (fields
        (field (name "Manufacturer Part") "0805W8F1002T5E")
        (field (name "Manufacturer") "UNI-ROYAL(厚声)")
      )
      (libsource (lib "easyedapro") (part "0805W8F1002T5E"))
    )
    (comp (ref "R19")
      (value "10kΩ")
      (footprint "easyedapro:R0805")
      (fields
        (field (name "Manufacturer Part") "0805W8F1002T5E")
        (field (name "Manufacturer") "UNI-ROYAL(厚声)")
      )
      (libsource (lib "easyedapro") (part "0805W8F1002T5E"))
    )
    (comp (ref "R20")
      (value "10kΩ")
      (footprint "easyedapro:R0805")
      (fields
        (field (name "Manufacturer Part") "0805W8F1002T5E")
        (field (name "Manufacturer") "UNI-ROYAL(厚声)")
      )
      (libsource (lib "easyedapro") (part "0805W8F1002T5E"))
    )
    (comp (ref "R21")
      (value "10kΩ")
      (footprint "easyedapro:R0805")
      (fields
        (field (name "Manufacturer Part") "0805W8F1002T5E")
        (field (name "Manufacturer") "UNI-ROYAL(厚声)")
      )
      (libsource (lib "easyedapro") (part "0805W8F1002T5E"))
    )
    (comp (ref "R22")
      (value "10kΩ")
      (footprint "easyedapro:R0805")
      (fields
        (field (name "Manufacturer Part") "0805W8F1002T5E")
        (field (name "Manufacturer") "UNI-ROYAL(厚声)")
      )
      (libsource (lib "easyedapro") (part "0805W8F1002T5E"))
    )
    (comp (ref "R30")
      (value "1kΩ")
      (footprint "easyedapro:R0603")
      (fields
        (field (name "Manufacturer Part") "0603WAF1001T5E")
        (field (name "Manufacturer") "UNI-ROYAL(厚声)")
      )
      (libsource (lib "easyedapro") (part "0603WAF1001T5E"))
    )
    (comp (ref "R31")
      (value "1kΩ")
      (footprint "easyedapro:R0603")
      (fields
        (field (name "Manufacturer Part") "0603WAF1001T5E")
        (field (name "Manufacturer") "UNI-ROYAL(厚声)")
      )
      (libsource (lib "easyedapro") (part "0603WAF1001T5E"))
    )
    (comp (ref "R32")
      (value "10kΩ")
      (footprint "easyedapro:R0805")
      (fields
        (field (name "Manufacturer Part") "0805W8F1002T5E")
        (field (name "Manufacturer") "UNI-ROYAL(厚声)")
      )
      (libsource (lib "easyedapro") (part "0805W8F1002T5E"))
    )
    (comp (ref "SW3")
      (value "SKQMBBE010")
      (footprint "easyedapro:KEY-SMD_L6.0-W3.5-LS6.2")
      (fields (field (name "Manufacturer") "ALPSALPINE(阿尔卑斯阿尔派)"))
      (libsource (lib "easyedapro") (part "SKQMBBE010"))
    )
    (comp (ref "SW4")
      (value "SKQMBBE010")
      (footprint "easyedapro:KEY-SMD_L6.0-W3.5-LS6.2")
      (fields (field (name "Manufacturer") "ALPSALPINE(阿尔卑斯阿尔派)"))
      (libsource (lib "easyedapro") (part "SKQMBBE010"))
    )
    (comp (ref "TP10")
      (value "~")
      (footprint "easyedapro:Test-Point-0.5mm")
      (description "Test Point 测试点")
      (libsource (lib "easyedapro") (part "Test-Point"))
    )
    (comp (ref "TP11")
      (value "~")
      (footprint "easyedapro:Test-Point-0.5mm")
      (description "Test Point 测试点")
      (libsource (lib "easyedapro") (part "Test-Point"))
    )
    (comp (ref "TP12")
      (value "~")
      (footprint "easyedapro:Test-Point-0.5mm")
      (description "Test Point 测试点")
      (libsource (lib "easyedapro") (part "Test-Point"))
    )
    (comp (ref "TP13")
      (value "~")
      (footprint "easyedapro:Test-Point-0.5mm")
      (description "Test Point 测试点")
      (libsource (lib "easyedapro") (part "Test-Point"))
    )
    (comp (ref "U4")
      (value "2.4GHz")
      (footprint "easyedapro:WIFIM-SMD_ESP32-S3-WROOM-1-N8")
      (description "Core Processor:ESP32-S3 Chip Support Interface:I2C；GPIO；SPI；PWM；ADC；UART；USB；I2S Frequency:2.4GHz")
      (fields
        (field (name "Manufacturer Part") "ESP32-S3-WROOM-1-N8")
        (field (name "Manufacturer") "ESPRESSIF(乐鑫)")
      )
      (libsource (lib "easyedapro") (part "ESP32-S3-WROOM-1-N8"))
    )
    (comp (ref "U19")
      (value "KF128-2.54-3P")
      (footprint "easyedapro:CONN-TH_3P-P2.54_KF128-2.54-3P")
      (fields (field (name "Manufacturer") "KEFA(科发)"))
      (libsource (lib "easyedapro") (part "KF128-2.54-3P"))
    )
    (comp (ref "U20")
      (value "KF128-2.54-3P")
      (footprint "easyedapro:CONN-TH_3P-P2.54_KF128-2.54-3P")
      (fields (field (name "Manufacturer") "KEFA(科发)"))
      (libsource (lib "easyedapro") (part "KF128-2.54-3P"))
    )
    (comp (ref "U25")
      (value "PAD_D3.3_M3Screw_1")
      (footprint "easyedapro:SMD_BD5.5-D3.9")
      (libsource (lib "easyedapro") (part "PAD_D3.3_M3SCREW_1"))
    )
    (comp (ref "U26")
      (value "PAD_D3.3_M3Screw_1")
      (footprint "easyedapro:SMD_BD5.5-D3.9")
      (libsource (lib "easyedapro") (part "PAD_D3.3_M3SCREW_1"))
    )
    (comp (ref "U27")
      (value "PAD_D3.3_M3Screw_1")
      (footprint "easyedapro:SMD_BD5.5-D3.9")
      (libsource (lib "easyedapro") (part "PAD_D3.3_M3SCREW_1"))
    )
    (comp (ref "U28")
      (value "PAD_D3.3_M3Screw_1")
      (footprint "easyedapro:SMD_BD5.5-D3.9")
      (libsource (lib "easyedapro") (part "PAD_D3.3_M3SCREW_1"))
    )
  )
  (nets
    (net (code "1") (name "+3V3") (class "Default")
      (node (ref "C16") (pin "2") (pinfunction "2_2") (pintype "input"))
      (node (ref "C37") (pin "2") (pinfunction "2_2") (pintype "input"))
      (node (ref "C38") (pin "2") (pinfunction "2_2") (pintype "input"))
      (node (ref "L10") (pin "1") (pinfunction "1_1") (pintype "unspecified"))
      (node (ref "L13") (pin "1") (pinfunction "1_1") (pintype "unspecified"))
      (node (ref "LED4") (pin "1") (pinfunction "+_1") (pintype "unspecified"))
      (node (ref "LED5") (pin "1") (pinfunction "A_1") (pintype "unspecified"))
      (node (ref "R15") (pin "2") (pinfunction "2_2") (pintype "input"))
      (node (ref "TP2") (pin "1") (pinfunction "1_1") (pintype "unspecified"))
      (node (ref "TP8") (pin "1") (pinfunction "1_1") (pintype "unspecified"))
      (node (ref "U6") (pin "4") (pinfunction "V3_4") (pintype "unspecified"))
      (node (ref "U9") (pin "2") (pinfunction "VOUT_2") (pintype "unspecified"))
      (node (ref "U9") (pin "4") (pinfunction "VOUT_4") (pintype "unspecified"))
    )
    (net (code "2") (name "+4V") (class "Default")
      (node (ref "C24") (pin "2") (pinfunction "2_2") (pintype "input"))
      (node (ref "C25") (pin "2") (pinfunction "2_2") (pintype "input"))
      (node (ref "C28") (pin "2") (pinfunction "2_2") (pintype "input"))
      (node (ref "C29") (pin "2") (pinfunction "2_2") (pintype "input"))
      (node (ref "C30") (pin "2") (pinfunction "2_2") (pintype "input"))
      (node (ref "C31") (pin "2") (pinfunction "2_2") (pintype "input"))
      (node (ref "C32") (pin "1") (pinfunction "1_1") (pintype "input"))
      (node (ref "C33") (pin "2") (pinfunction "2_2") (pintype "input"))
      (node (ref "TP14") (pin "1") (pinfunction "1_1") (pintype "unspecified"))
      (node (ref "TP16") (pin "1") (pinfunction "1_1") (pintype "unspecified"))
      (node (ref "TP17") (pin "1") (pinfunction "1_1") (pintype "unspecified"))
      (node (ref "TP18") (pin "1") (pinfunction "1_1") (pintype "unspecified"))
      (node (ref "TP19") (pin "1") (pinfunction "1_1") (pintype "unspecified"))
      (node (ref "TP20") (pin "1") (pinfunction "1_1") (pintype "unspecified"))
      (node (ref "U1") (pin "27") (pinfunction "Vin_27") (pintype "unspecified"))
      (node (ref "U10") (pin "10") (pinfunction "OUT_10") (pintype "unspecified"))
      (node (ref "U10") (pin "9") (pinfunction "OUTS_9") (pintype "unspecified"))
      (node (ref "U12") (pin "14") (pinfunction "VDD_14") (pintype "unspecified"))
      (node (ref "U12") (pin "2") (pinfunction "EN_2") (pintype "unspecified"))
      (node (ref "U13") (pin "14") (pinfunction "VDD_14") (pintype "unspecified"))
      (node (ref "U13") (pin "2") (pinfunction "EN_2") (pintype "unspecified"))
    )
    (net (code "3") (name "+5V") (class "Default")
      (node (ref "C15") (pin "2") (pinfunction "2_2") (pintype "input"))
      (node (ref "C26") (pin "2") (pinfunction "2_2") (pintype "input"))
      (node (ref "C27") (pin "2") (pinfunction "2_2") (pintype "input"))
      (node (ref "C36") (pin "2") (pinfunction "2_2") (pintype "input"))
      (node (ref "LED1") (pin "2") (pinfunction "A_2") (pintype "unspecified"))
      (node (ref "TP15") (pin "1") (pinfunction "1_1") (pintype "unspecified"))
      (node (ref "TP3") (pin "1") (pinfunction "1_1") (pintype "unspecified"))
      (node (ref "U10") (pin "1") (pinfunction "IN_1") (pintype "unspecified"))
      (node (ref "U10") (pin "2") (pinfunction "IN_2") (pintype "unspecified"))
      (node (ref "U10") (pin "3") (pinfunction "EN/UV_3") (pintype "unspecified"))
      (node (ref "U10") (pin "6") (pinfunction "PGFB_6") (pintype "unspecified"))
      (node (ref "U8") (pin "2") (pinfunction "VOUT_2") (pintype "unspecified"))
      (node (ref "U8") (pin "7") (pinfunction "VOUT_7") (pintype "unspecified"))
      (node (ref "U9") (pin "3") (pinfunction "VIN_3") (pintype "unspecified"))
    )
    (net (code "4") (name "+5V_USB1") (class "Default")
      (node (ref "C2") (pin "2") (pinfunction "2_2") (pintype "input"))
      (node (ref "C22") (pin "2") (pinfunction "2_2") (pintype "input"))
      (node (ref "C6") (pin "2") (pinfunction "2_2") (pintype "input"))
      (node (ref "L3") (pin "2") (pinfunction "2_2") (pintype "unspecified"))
      (node (ref "R14") (pin "2") (pinfunction "2_2") (pintype "input"))
      (node (ref "TP1") (pin "1") (pinfunction "1_1") (pintype "unspecified"))
      (node (ref "TP4") (pin "1") (pinfunction "1_1") (pintype "unspecified"))
      (node (ref "U5") (pin "12") (pinfunction "VCC_12") (pintype "unspecified"))
      (node (ref "U8") (pin "3") (pinfunction "VIN1_3") (pintype "unspecified"))
    )
    (net (code "5") (name "+5V_USB2") (class "Default")
      (node (ref "C10") (pin "2") (pinfunction "2_2") (pintype "input"))
      (node (ref "C13") (pin "2") (pinfunction "2_2") (pintype "input"))
      (node (ref "C21") (pin "2") (pinfunction "2_2") (pintype "input"))
      (node (ref "L7") (pin "2") (pinfunction "2_2") (pintype "unspecified"))
      (node (ref "TP5") (pin "1") (pinfunction "1_1") (pintype "unspecified"))
      (node (ref "TP6") (pin "1") (pinfunction "1_1") (pintype "unspecified"))
      (node (ref "TP7") (pin "1") (pinfunction "1_1") (pintype "unspecified"))
      (node (ref "U6") (pin "16") (pinfunction "VCC_16") (pintype "unspecified"))
      (node (ref "U8") (pin "6") (pinfunction "VIN2_6") (pintype "unspecified"))
    )
    (net (code "6") (name "CE1") (class "Default")
      (node (ref "U12") (pin "4") (pinfunction "S1A_4") (pintype "unspecified"))
      (node (ref "U17") (pin "3") (pinfunction "3_3") (pintype "input"))
    )
    (net (code "7") (name "CE2") (class "Default")
      (node (ref "U12") (pin "5") (pinfunction "S2A_5") (pintype "unspecified"))
      (node (ref "U17") (pin "2") (pinfunction "2_2") (pintype "input"))
    )
    (net (code "8") (name "CE3") (class "Default")
      (node (ref "U12") (pin "6") (pinfunction "S3A_6") (pintype "unspecified"))
      (node (ref "U17") (pin "1") (pinfunction "1_1") (pintype "input"))
    )
    (net (code "9") (name "CE_RE_MUX_0") (class "Default")
      (node (ref "SW2") (pin "11") (pinfunction "B6_11") (pintype "input"))
      (node (ref "SW2") (pin "15") (pinfunction "B2_15") (pintype "input"))
      (node (ref "TP23") (pin "1") (pinfunction "1_1") (pintype "unspecified"))
      (node (ref "U12") (pin "1") (pinfunction "A0_1") (pintype "unspecified"))
    )
    (net (code "10") (name "CE_RE_MUX_1") (class "Default")
      (node (ref "SW2") (pin "12") (pinfunction "B5_12") (pintype "input"))
      (node (ref "SW2") (pin "16") (pinfunction "B1_16") (pintype "input"))
      (node (ref "TP24") (pin "1") (pinfunction "1_1") (pintype "unspecified"))
      (node (ref "U12") (pin "16") (pinfunction "A1_16") (pintype "unspecified"))
    )
    (net (code "11") (name "D+") (class "Default")
      (node (ref "R5") (pin "1") (pinfunction "1_1") (pintype "input"))
      (node (ref "U21") (pin "2") (pinfunction "2_2") (pintype "unspecified"))
      (node (ref "USBC1") (pin "A6") (pinfunction "DP1_A6") (pintype "unspecified"))
      (node (ref "USBC1") (pin "B6") (pinfunction "DP2_B6") (pintype "unspecified"))
    )
    (net (code "12") (name "D-") (class "Default")
      (node (ref "R4") (pin "1") (pinfunction "1_1") (pintype "input"))
      (node (ref "U22") (pin "2") (pinfunction "2_2") (pintype "unspecified"))
      (node (ref "USBC1") (pin "A7") (pinfunction "DN1_A7") (pintype "unspecified"))
      (node (ref "USBC1") (pin "B7") (pinfunction "DN2_B7") (pintype "unspecified"))
    )
    (net (code "13") (name "DN") (class "Default")
      (node (ref "U24") (pin "2") (pinfunction "2_2") (pintype "unspecified"))
      (node (ref "U6") (pin "6") (pinfunction "D-_6") (pintype "unspecified"))
      (node (ref "USBC2") (pin "A7") (pinfunction "DN1_A7") (pintype "unspecified"))
      (node (ref "USBC2") (pin "B7") (pinfunction "DN2_B7") (pintype "unspecified"))
    )
    (net (code "14") (name "DP") (class "Default")
      (node (ref "U23") (pin "2") (pinfunction "2_2") (pintype "unspecified"))
      (node (ref "U6") (pin "5") (pinfunction "D+_5") (pintype "unspecified"))
      (node (ref "USBC2") (pin "A6") (pinfunction "DP1_A6") (pintype "unspecified"))
      (node (ref "USBC2") (pin "B6") (pinfunction "DP2_B6") (pintype "unspecified"))
    )
    (net (code "15") (name "DTR") (class "Default")
      (node (ref "Q2") (pin "2") (pinfunction "E_2") (pintype "unspecified"))
      (node (ref "R7") (pin "1") (pinfunction "1_1") (pintype "input"))
      (node (ref "U6") (pin "13") (pinfunction "DTR#_13") (pintype "unspecified"))
    )
    (net (code "16") (name "ESP_CE_RE_MUX_0") (class "Default")
      (node (ref "SW2") (pin "2") (pinfunction "A2_2") (pintype "input"))
      (node (ref "U4") (pin "6") (pinfunction "IO6_6") (pintype "unspecified"))
    )
    (net (code "17") (name "ESP_CE_RE_MUX_1") (class "Default")
      (node (ref "SW2") (pin "1") (pinfunction "A1_1") (pintype "input"))
      (node (ref "U4") (pin "7") (pinfunction "IO7_7") (pintype "unspecified"))
    )
    (net (code "18") (name "ESP_EN") (class "Default")
      (node (ref "C14") (pin "2") (pinfunction "2_2") (pintype "input"))
      (node (ref "C40") (pin "2") (pinfunction "2_2") (pintype "input"))
      (node (ref "R15") (pin "1") (pinfunction "1_1") (pintype "input"))
      (node (ref "R9") (pin "2") (pinfunction "2_2") (pintype "input"))
      (node (ref "SW4") (pin "1") (pinfunction "1_1") (pintype "input"))
      (node (ref "TP12") (pin "1") (pinfunction "1_1") (pintype "unspecified"))
      (node (ref "U4") (pin "3") (pinfunction "EN_3") (pintype "unspecified"))
    )
    (net (code "19") (name "ESP_GPIO0") (class "Default")
      (node (ref "C39") (pin "2") (pinfunction "2_2") (pintype "input"))
      (node (ref "R10") (pin "2") (pinfunction "2_2") (pintype "input"))
      (node (ref "SW3") (pin "1") (pinfunction "1_1") (pintype "input"))
      (node (ref "U4") (pin "27") (pinfunction "IO0_27") (pintype "unspecified"))
    )
    (net (code "20") (name "ESP_RX0") (class "Default")
      (node (ref "U4") (pin "36") (pinfunction "RXD0_36") (pintype "unspecified"))
      (node (ref "U6") (pin "2") (pinfunction "TXD_2") (pintype "unspecified"))
    )
    (net (code "21") (name "ESP_RX_1") (class "Default")
      (node (ref "SW1") (pin "4") (pinfunction "A4_4") (pintype "input"))
      (node (ref "U4") (pin "11") (pinfunction "IO18_11") (pintype "unspecified"))
    )
    (net (code "22") (name "ESP_TX0") (class "Default")
      (node (ref "U4") (pin "37") (pinfunction "TXD0_37") (pintype "unspecified"))
      (node (ref "U6") (pin "3") (pinfunction "RXD_3") (pintype "unspecified"))
    )
    (net (code "23") (name "ESP_TX_1") (class "Default")
      (node (ref "SW1") (pin "3") (pinfunction "A3_3") (pintype "input"))
      (node (ref "U4") (pin "10") (pinfunction "IO17_10") (pintype "unspecified"))
    )
    (net (code "24") (name "ESP_WE_MUX_0") (class "Default")
      (node (ref "SW2") (pin "4") (pinfunction "A4_4") (pintype "input"))
      (node (ref "U4") (pin "4") (pinfunction "IO4_4") (pintype "unspecified"))
    )
    (net (code "25") (name "ESP_WE_MUX_1") (class "Default")
      (node (ref "SW2") (pin "3") (pinfunction "A3_3") (pintype "input"))
      (node (ref "U4") (pin "5") (pinfunction "IO5_5") (pintype "unspecified"))
    )
    (net (code "26") (name "FTDI_RX") (class "Default")
      (node (ref "SW1") (pin "2") (pinfunction "A2_2") (pintype "input"))
      (node (ref "U5") (pin "4") (pinfunction "RXD_4") (pintype "unspecified"))
    )
    (net (code "27") (name "FTDI_TX") (class "Default")
      (node (ref "SW1") (pin "1") (pinfunction "A1_1") (pintype "input"))
      (node (ref "U5") (pin "1") (pinfunction "TXD_1") (pintype "output"))
    )
    (net (code "28") (name "GND") (class "Default")
      (node (ref "C1") (pin "1") (pinfunction "1_1") (pintype "input"))
      (node (ref "C10") (pin "1") (pinfunction "1_1") (pintype "input"))
      (node (ref "C12") (pin "2") (pinfunction "2_2") (pintype "input"))
      (node (ref "C13") (pin "1") (pinfunction "1_1") (pintype "input"))
      (node (ref "C14") (pin "1") (pinfunction "1_1") (pintype "input"))
      (node (ref "C15") (pin "1") (pinfunction "1_1") (pintype "input"))
      (node (ref "C16") (pin "1") (pinfunction "1_1") (pintype "input"))
      (node (ref "C17") (pin "1") (pinfunction "1_1") (pintype "input"))
      (node (ref "C18") (pin "1") (pinfunction "1_1") (pintype "unspecified"))
      (node (ref "C2") (pin "1") (pinfunction "1_1") (pintype "input"))
      (node (ref "C21") (pin "1") (pinfunction "1_1") (pintype "input"))
      (node (ref "C22") (pin "1") (pinfunction "1_1") (pintype "input"))
      (node (ref "C23") (pin "1") (pinfunction "1_1") (pintype "input"))
      (node (ref "C24") (pin "1") (pinfunction "1_1") (pintype "input"))
      (node (ref "C25") (pin "1") (pinfunction "1_1") (pintype "input"))
      (node (ref "C26") (pin "1") (pinfunction "1_1") (pintype "input"))
      (node (ref "C27") (pin "1") (pinfunction "1_1") (pintype "input"))
      (node (ref "C28") (pin "1") (pinfunction "1_1") (pintype "input"))
      (node (ref "C29") (pin "1") (pinfunction "1_1") (pintype "input"))
      (node (ref "C30") (pin "1") (pinfunction "1_1") (pintype "input"))
      (node (ref "C31") (pin "1") (pinfunction "1_1") (pintype "input"))
      (node (ref "C32") (pin "2") (pinfunction "2_2") (pintype "input"))
      (node (ref "C33") (pin "1") (pinfunction "1_1") (pintype "input"))
      (node (ref "C34") (pin "1") (pinfunction "1_1") (pintype "input"))
      (node (ref "C35") (pin "1") (pinfunction "1_1") (pintype "unspecified"))
      (node (ref "C36") (pin "1") (pinfunction "1_1") (pintype "input"))
      (node (ref "C37") (pin "1") (pinfunction "1_1") (pintype "input"))
      (node (ref "C38") (pin "1") (pinfunction "1_1") (pintype "input"))
      (node (ref "C39") (pin "1") (pinfunction "1_1") (pintype "input"))
      (node (ref "C4") (pin "2") (pinfunction "2_2") (pintype "input"))
      (node (ref "C40") (pin "1") (pinfunction "1_1") (pintype "input"))
      (node (ref "C5") (pin "1") (pinfunction "1_1") (pintype "input"))
      (node (ref "C6") (pin "1") (pinfunction "1_1") (pintype "input"))
      (node (ref "C9") (pin "1") (pinfunction "1_1") (pintype "input"))
      (node (ref "CARD3") (pin "10") (pinfunction "GND_10") (pintype "input"))
      (node (ref "CARD3") (pin "11") (pinfunction "GND_11") (pintype "input"))
      (node (ref "CARD3") (pin "12") (pinfunction "GND_12") (pintype "input"))
      (node (ref "CARD3") (pin "13") (pinfunction "GND_13") (pintype "input"))
      (node (ref "CARD3") (pin "6") (pinfunction "VSS_6") (pintype "input"))
      (node (ref "D1") (pin "1") (pinfunction "1_1") (pintype "unspecified"))
      (node (ref "D2") (pin "1") (pinfunction "1_1") (pintype "unspecified"))
      (node (ref "R1") (pin "1") (pinfunction "1_1") (pintype "input"))
      (node (ref "R11") (pin "1") (pinfunction "1_1") (pintype "input"))
      (node (ref "R12") (pin "1") (pinfunction "1_1") (pintype "input"))
      (node (ref "R13") (pin "2") (pinfunction "2_2") (pintype "input"))
      (node (ref "R16") (pin "1") (pinfunction "1_1") (pintype "unspecified"))
      (node (ref "R2") (pin "1") (pinfunction "1_1") (pintype "input"))
      (node (ref "R29") (pin "1") (pinfunction "1_1") (pintype "input"))
      (node (ref "R3") (pin "2") (pinfunction "2_2") (pintype "input"))
      (node (ref "SW3") (pin "2") (pinfunction "2_2") (pintype "input"))
      (node (ref "SW4") (pin "2") (pinfunction "2_2") (pintype "input"))
      (node (ref "U1") (pin "15") (pinfunction "AGND_15") (pintype "unspecified"))
      (node (ref "U1") (pin "28") (pinfunction "DGND_28") (pintype "unspecified"))
      (node (ref "U1") (pin "8") (pinfunction "DGND_8") (pintype "unspecified"))
      (node (ref "U10") (pin "11") (pinfunction "GND_11") (pintype "unspecified"))
      (node (ref "U10") (pin "5") (pinfunction "ILIM_5") (pintype "unspecified"))
      (node (ref "U10") (pin "8") (pinfunction "GND_8") (pintype "unspecified"))
      (node (ref "U12") (pin "15") (pinfunction "GND_15") (pintype "unspecified"))
      (node (ref "U12") (pin "3") (pinfunction "VSS_3") (pintype "unspecified"))
      (node (ref "U13") (pin "15") (pinfunction "GND_15") (pintype "unspecified"))
      (node (ref "U13") (pin "3") (pinfunction "VSS_3") (pintype "unspecified"))
      (node (ref "U20") (pin "3") (pinfunction "3_3") (pintype "input"))
      (node (ref "U21") (pin "1") (pinfunction "1_1") (pintype "unspecified"))
      (node (ref "U22") (pin "1") (pinfunction "1_1") (pintype "unspecified"))
      (node (ref "U23") (pin "1") (pinfunction "1_1") (pintype "unspecified"))
      (node (ref "U24") (pin "1") (pinfunction "1_1") (pintype "unspecified"))
      (node (ref "U25") (pin "1") (pinfunction "1_1") (pintype "unspecified"))
      (node (ref "U26") (pin "1") (pinfunction "1_1") (pintype "unspecified"))
      (node (ref "U27") (pin "1") (pinfunction "1_1") (pintype "unspecified"))
      (node (ref "U28") (pin "1") (pinfunction "1_1") (pintype "unspecified"))
      (node (ref "U4") (pin "1") (pinfunction "GND_1") (pintype "unspecified"))
      (node (ref "U4") (pin "40") (pinfunction "GND_40") (pintype "unspecified"))
      (node (ref "U4") (pin "41") (pinfunction "EP_41") (pintype "unspecified"))
      (node (ref "U5") (pin "13") (pinfunction "GND_13") (pintype "unspecified"))
      (node (ref "U5") (pin "5") (pinfunction "GND_5") (pintype "unspecified"))
      (node (ref "U6") (pin "1") (pinfunction "GND_1") (pintype "unspecified"))
      (node (ref "U8") (pin "1") (pinfunction "GND_1") (pintype "unspecified"))
      (node (ref "U8") (pin "4") (pinfunction "ON#_4") (pintype "unspecified"))
      (node (ref "U8") (pin "5") (pinfunction "GND_5") (pintype "unspecified"))
      (node (ref "U9") (pin "1") (pinfunction "GND_1") (pintype "unspecified"))
      (node (ref "USBC1") (pin "A1") (pinfunction "GND_A1") (pintype "unspecified"))
      (node (ref "USBC1") (pin "A12") (pinfunction "GND_A12") (pintype "unspecified"))
      (node (ref "USBC1") (pin "B1") (pinfunction "GND_B1") (pintype "unspecified"))
      (node (ref "USBC1") (pin "B12") (pinfunction "GND_B12") (pintype "unspecified"))
      (node (ref "USBC2") (pin "A1") (pinfunction "GND_A1") (pintype "unspecified"))
      (node (ref "USBC2") (pin "A12") (pinfunction "GND_A12") (pintype "unspecified"))
      (node (ref "USBC2") (pin "B1") (pinfunction "GND_B1") (pintype "unspecified"))
      (node (ref "USBC2") (pin "B12") (pinfunction "GND_B12") (pintype "unspecified"))
    )
    (net (code "29") (name "IO15") (class "Default")
      (node (ref "U20") (pin "1") (pinfunction "1_1") (pintype "input"))
      (node (ref "U4") (pin "8") (pinfunction "IO15_8") (pintype "unspecified"))
    )
    (net (code "30") (name "IO16") (class "Default")
      (node (ref "U20") (pin "2") (pinfunction "2_2") (pintype "input"))
      (node (ref "U4") (pin "9") (pinfunction "IO16_9") (pintype "unspecified"))
    )
    (net (code "31") (name "IO35") (class "Default")
      (node (ref "CARD3") (pin "1") (pinfunction "DAT2(RSV)_1") (pintype "bidirectional"))
      (node (ref "R20") (pin "1") (pinfunction "1_1") (pintype "input"))
      (node (ref "U4") (pin "28") (pinfunction "IO35_28") (pintype "unspecified"))
    )
    (net (code "32") (name "IO36") (class "Default")
      (node (ref "CARD3") (pin "2") (pinfunction "CDDAT3(CS)_2") (pintype "bidirectional"))
      (node (ref "R19") (pin "1") (pinfunction "1_1") (pintype "input"))
      (node (ref "U4") (pin "29") (pinfunction "IO36_29") (pintype "unspecified"))
    )
    (net (code "33") (name "IO37") (class "Default")
      (node (ref "CARD3") (pin "3") (pinfunction "CMD(DI)_3") (pintype "input"))
      (node (ref "R18") (pin "1") (pinfunction "1_1") (pintype "input"))
      (node (ref "U4") (pin "30") (pinfunction "IO37_30") (pintype "unspecified"))
    )
    (net (code "34") (name "IO38") (class "Default")
      (node (ref "CARD3") (pin "5") (pinfunction "CLK(SCLK)_5") (pintype "input"))
      (node (ref "U4") (pin "31") (pinfunction "IO38_31") (pintype "unspecified"))
    )
    (net (code "35") (name "IO39") (class "Default")
      (node (ref "CARD3") (pin "7") (pinfunction "DAT0(D0)_7") (pintype "bidirectional"))
      (node (ref "R22") (pin "1") (pinfunction "1_1") (pintype "input"))
      (node (ref "U4") (pin "32") (pinfunction "IO39_32") (pintype "unspecified"))
    )
    (net (code "36") (name "IO40") (class "Default")
      (node (ref "CARD3") (pin "8") (pinfunction "DAT1(RSV)_8") (pintype "bidirectional"))
      (node (ref "R21") (pin "1") (pinfunction "1_1") (pintype "input"))
      (node (ref "U4") (pin "33") (pinfunction "IO40_33") (pintype "unspecified"))
    )
    (net (code "37") (name "LED_GREEN") (class "Default")
      (node (ref "R31") (pin "1") (pinfunction "1_1") (pintype "input"))
      (node (ref "U4") (pin "19") (pinfunction "IO11_19") (pintype "unspecified"))
    )
    (net (code "38") (name "LED_YELLOW") (class "Default")
      (node (ref "R30") (pin "1") (pinfunction "1_1") (pintype "input"))
      (node (ref "U4") (pin "18") (pinfunction "IO10_18") (pintype "unspecified"))
    )
    (net (code "39") (name "Net-(C1-Pad2)") (class "Default")
      (node (ref "C1") (pin "2") (pinfunction "2_2") (pintype "input"))
      (node (ref "L2") (pin "2") (pinfunction "2_2") (pintype "unspecified"))
      (node (ref "L3") (pin "1") (pinfunction "1_1") (pintype "unspecified"))
    )
    (net (code "40") (name "Net-(C4-Pad1)") (class "Default")
      (node (ref "C4") (pin "1") (pinfunction "1_1") (pintype "input"))
      (node (ref "R3") (pin "1") (pinfunction "1_1") (pintype "input"))
      (node (ref "USBC1") (pin "0") (pinfunction "SH_0") (pintype "unspecified"))
      (node (ref "USBC1") (pin "1") (pinfunction "SH_1") (pintype "unspecified"))
      (node (ref "USBC1") (pin "2") (pinfunction "SH_2") (pintype "unspecified"))
      (node (ref "USBC1") (pin "3") (pinfunction "SH_3") (pintype "unspecified"))
    )
    (net (code "41") (name "Net-(C9-Pad2)") (class "Default")
      (node (ref "C9") (pin "2") (pinfunction "2_2") (pintype "input"))
      (node (ref "L6") (pin "2") (pinfunction "2_2") (pintype "unspecified"))
      (node (ref "L7") (pin "1") (pinfunction "1_1") (pintype "unspecified"))
    )
    (net (code "42") (name "Net-(C12-Pad1)") (class "Default")
      (node (ref "C12") (pin "1") (pinfunction "1_1") (pintype "input"))
      (node (ref "R13") (pin "1") (pinfunction "1_1") (pintype "input"))
      (node (ref "USBC2") (pin "0") (pinfunction "SH_0") (pintype "unspecified"))
      (node (ref "USBC2") (pin "1") (pinfunction "SH_1") (pintype "unspecified"))
      (node (ref "USBC2") (pin "2") (pinfunction "SH_2") (pintype "unspecified"))
      (node (ref "USBC2") (pin "3") (pinfunction "SH_3") (pintype "unspecified"))
    )
    (net (code "43") (name "Net-(LED1-K)") (class "Default")
      (node (ref "LED1") (pin "1") (pinfunction "K_1") (pintype "unspecified"))
      (node (ref "R29") (pin "2") (pinfunction "2_2") (pintype "input"))
    )
    (net (code "44") (name "Net-(LED4--)") (class "Default")
      (node (ref "LED4") (pin "2") (pinfunction "-_2") (pintype "unspecified"))
      (node (ref "R30") (pin "2") (pinfunction "2_2") (pintype "input"))
    )
    (net (code "45") (name "Net-(LED5-K)") (class "Default")
      (node (ref "LED5") (pin "2") (pinfunction "K_2") (pintype "unspecified"))
      (node (ref "R31") (pin "2") (pinfunction "2_2") (pintype "input"))
    )
    (net (code "46") (name "Net-(Q1-B)") (class "Default")
      (node (ref "Q1") (pin "1") (pinfunction "B_1") (pintype "unspecified"))
      (node (ref "R7") (pin "2") (pinfunction "2_2") (pintype "input"))
    )
    (net (code "47") (name "Net-(Q1-C)") (class "Default")
      (node (ref "Q1") (pin "3") (pinfunction "C_3") (pintype "unspecified"))
      (node (ref "R9") (pin "1") (pinfunction "1_1") (pintype "input"))
    )
    (net (code "48") (name "Net-(Q2-B)") (class "Default")
      (node (ref "Q2") (pin "1") (pinfunction "B_1") (pintype "unspecified"))
      (node (ref "R8") (pin "2") (pinfunction "2_2") (pintype "input"))
    )
    (net (code "49") (name "Net-(Q2-C)") (class "Default")
      (node (ref "Q2") (pin "3") (pinfunction "C_3") (pintype "unspecified"))
      (node (ref "R10") (pin "1") (pinfunction "1_1") (pintype "input"))
    )
    (net (code "50") (name "Net-(SW1-B1)") (class "Default")
      (node (ref "SW1") (pin "6") (pinfunction "B3_6") (pintype "input"))
      (node (ref "SW1") (pin "8") (pinfunction "B1_8") (pintype "input"))
      (node (ref "U1") (pin "2") (pinfunction "RX_2") (pintype "input"))
    )
    (net (code "51") (name "Net-(SW1-B2)") (class "Default")
      (node (ref "SW1") (pin "5") (pinfunction "B4_5") (pintype "input"))
      (node (ref "SW1") (pin "7") (pinfunction "B2_7") (pintype "input"))
      (node (ref "U1") (pin "3") (pinfunction "TX_3") (pintype "output"))
    )
    (net (code "52") (name "Net-(U4-3V3)") (class "Default")
      (node (ref "C17") (pin "2") (pinfunction "2_2") (pintype "input"))
      (node (ref "C18") (pin "2") (pinfunction "2_2") (pintype "unspecified"))
      (node (ref "L10") (pin "2") (pinfunction "2_2") (pintype "unspecified"))
      (node (ref "TP13") (pin "1") (pinfunction "1_1") (pintype "unspecified"))
      (node (ref "U4") (pin "2") (pinfunction "3V3_2") (pintype "unspecified"))
    )
    (net (code "53") (name "Net-(U5-3V3OUT)") (class "Default")
      (node (ref "C5") (pin "2") (pinfunction "2_2") (pintype "input"))
      (node (ref "TP9") (pin "1") (pinfunction "1_1") (pintype "unspecified"))
      (node (ref "U5") (pin "10") (pinfunction "3V3OUT_10") (pintype "unspecified"))
      (node (ref "U5") (pin "11") (pinfunction "RESET#_11") (pintype "unspecified"))
      (node (ref "U5") (pin "3") (pinfunction "VCCIO_3") (pintype "unspecified"))
    )
    (net (code "54") (name "Net-(U5-USBDM)") (class "Default")
      (node (ref "R4") (pin "2") (pinfunction "2_2") (pintype "input"))
      (node (ref "U5") (pin "9") (pinfunction "USBDM_9") (pintype "unspecified"))
    )
    (net (code "55") (name "Net-(U5-USBDP)") (class "Default")
      (node (ref "R5") (pin "2") (pinfunction "2_2") (pintype "input"))
      (node (ref "U5") (pin "8") (pinfunction "USBDP_8") (pintype "unspecified"))
    )
    (net (code "56") (name "Net-(U8-ST)") (class "Default")
      (node (ref "R14") (pin "1") (pinfunction "1_1") (pintype "input"))
      (node (ref "U8") (pin "8") (pinfunction "ST_8") (pintype "unspecified"))
    )
    (net (code "57") (name "Net-(U10-SET)") (class "Default")
      (node (ref "C23") (pin "2") (pinfunction "2_2") (pintype "input"))
      (node (ref "R16") (pin "2") (pinfunction "2_2") (pintype "unspecified"))
      (node (ref "U10") (pin "7") (pinfunction "SET_7") (pintype "unspecified"))
    )
    (net (code "58") (name "Net-(USBC1-CC1)") (class "Default")
      (node (ref "R1") (pin "2") (pinfunction "2_2") (pintype "input"))
      (node (ref "USBC1") (pin "A5") (pinfunction "CC1_A5") (pintype "unspecified"))
    )
    (net (code "59") (name "Net-(USBC1-CC2)") (class "Default")
      (node (ref "R2") (pin "2") (pinfunction "2_2") (pintype "input"))
      (node (ref "USBC1") (pin "B5") (pinfunction "CC2_B5") (pintype "unspecified"))
    )
    (net (code "60") (name "Net-(USBC2-CC1)") (class "Default")
      (node (ref "R11") (pin "2") (pinfunction "2_2") (pintype "input"))
      (node (ref "USBC2") (pin "A5") (pinfunction "CC1_A5") (pintype "unspecified"))
    )
    (net (code "61") (name "Net-(USBC2-CC2)") (class "Default")
      (node (ref "R12") (pin "2") (pinfunction "2_2") (pintype "input"))
      (node (ref "USBC2") (pin "B5") (pinfunction "CC2_B5") (pintype "unspecified"))
    )
    (net (code "62") (name "PICO_CE0") (class "Default")
      (node (ref "U1") (pin "18") (pinfunction "CE_0_18") (pintype "input"))
      (node (ref "U12") (pin "8") (pinfunction "DA_8") (pintype "unspecified"))
    )
    (net (code "63") (name "PICO_CE_RE_MUX_0") (class "Default")
      (node (ref "SW2") (pin "6") (pinfunction "A6_6") (pintype "input"))
      (node (ref "U1") (pin "9") (pinfunction "GPIO_2_9") (pintype "input"))
    )
    (net (code "64") (name "PICO_CE_RE_MUX_1") (class "Default")
      (node (ref "SW2") (pin "5") (pinfunction "A5_5") (pintype "input"))
      (node (ref "U1") (pin "10") (pinfunction "GPIO_3_10") (pintype "bidirectional"))
    )
    (net (code "65") (name "PICO_DWNLD") (class "Default")
      (node (ref "U1") (pin "4") (pinfunction "DWN_4") (pintype "input"))
      (node (ref "U5") (pin "15") (pinfunction "CBUS0_15") (pintype "bidirectional"))
    )
    (net (code "66") (name "PICO_RE0") (class "Default")
      (node (ref "U1") (pin "16") (pinfunction "RE_0_16") (pintype "input"))
      (node (ref "U12") (pin "9") (pinfunction "DB_9") (pintype "unspecified"))
    )
    (net (code "67") (name "PICO_RESET") (class "Default")
      (node (ref "U1") (pin "5") (pinfunction "RST_5") (pintype "input"))
      (node (ref "U5") (pin "14") (pinfunction "CBUS1_14") (pintype "bidirectional"))
    )
    (net (code "68") (name "PICO_WE0") (class "Default")
      (node (ref "U1") (pin "17") (pinfunction "WE_0_17") (pintype "input"))
      (node (ref "U13") (pin "8") (pinfunction "DA_8") (pintype "unspecified"))
    )
    (net (code "69") (name "PICO_WE_MUX_0") (class "Default")
      (node (ref "SW2") (pin "8") (pinfunction "A8_8") (pintype "input"))
      (node (ref "U1") (pin "6") (pinfunction "GPIO_0_6") (pintype "bidirectional"))
    )
    (net (code "70") (name "PICO_WE_MUX_1") (class "Default")
      (node (ref "SW2") (pin "7") (pinfunction "A7_7") (pintype "input"))
      (node (ref "U1") (pin "7") (pinfunction "GPIO_1_7") (pintype "bidirectional"))
    )
    (net (code "71") (name "RE1") (class "Default")
      (node (ref "U12") (pin "13") (pinfunction "S1B_13") (pintype "unspecified"))
      (node (ref "U15") (pin "1") (pinfunction "1_1") (pintype "input"))
    )
    (net (code "72") (name "RE2") (class "Default")
      (node (ref "U12") (pin "12") (pinfunction "S2B_12") (pintype "unspecified"))
      (node (ref "U15") (pin "2") (pinfunction "2_2") (pintype "input"))
    )
    (net (code "73") (name "RE3") (class "Default")
      (node (ref "U12") (pin "11") (pinfunction "S3B_11") (pintype "unspecified"))
      (node (ref "U15") (pin "3") (pinfunction "3_3") (pintype "input"))
    )
    (net (code "74") (name "REGEN_1") (class "Default")
      (node (ref "U19") (pin "1") (pinfunction "1_1") (pintype "input"))
      (node (ref "U4") (pin "23") (pinfunction "IO21_23") (pintype "unspecified"))
    )
    (net (code "75") (name "REGEN_2") (class "Default")
      (node (ref "U19") (pin "2") (pinfunction "2_2") (pintype "input"))
      (node (ref "U4") (pin "24") (pinfunction "IO47_24") (pintype "unspecified"))
    )
    (net (code "76") (name "REGEN_3") (class "Default")
      (node (ref "U19") (pin "3") (pinfunction "3_3") (pintype "input"))
      (node (ref "U4") (pin "25") (pinfunction "IO48_25") (pintype "unspecified"))
    )
    (net (code "77") (name "RTS") (class "Default")
      (node (ref "Q1") (pin "2") (pinfunction "E_2") (pintype "unspecified"))
      (node (ref "R8") (pin "1") (pinfunction "1_1") (pintype "input"))
      (node (ref "U6") (pin "14") (pinfunction "RTS#_14") (pintype "unspecified"))
    )
    (net (code "78") (name "SD_CD") (class "Default")
      (node (ref "CARD3") (pin "9") (pinfunction "CD_9") (pintype "input"))
      (node (ref "R32") (pin "1") (pinfunction "1_1") (pintype "input"))
      (node (ref "U4") (pin "34") (pinfunction "IO41_34") (pintype "unspecified"))
    )
    (net (code "79") (name "VBUS1") (class "Default")
      (node (ref "D1") (pin "2") (pinfunction "2_2") (pintype "unspecified"))
      (node (ref "L2") (pin "1") (pinfunction "1_1") (pintype "unspecified"))
      (node (ref "USBC1") (pin "A4") (pinfunction "VBUS_A4") (pintype "unspecified"))
      (node (ref "USBC1") (pin "A9") (pinfunction "VBUS_A9") (pintype "unspecified"))
      (node (ref "USBC1") (pin "B4") (pinfunction "VBUS_B4") (pintype "unspecified"))
      (node (ref "USBC1") (pin "B9") (pinfunction "VBUS_B9") (pintype "unspecified"))
    )
    (net (code "80") (name "VBUS2") (class "Default")
      (node (ref "D2") (pin "2") (pinfunction "2_2") (pintype "unspecified"))
      (node (ref "L6") (pin "1") (pinfunction "1_1") (pintype "unspecified"))
      (node (ref "USBC2") (pin "A4") (pinfunction "VBUS_A4") (pintype "unspecified"))
      (node (ref "USBC2") (pin "A9") (pinfunction "VBUS_A9") (pintype "unspecified"))
      (node (ref "USBC2") (pin "B4") (pinfunction "VBUS_B4") (pintype "unspecified"))
      (node (ref "USBC2") (pin "B9") (pinfunction "VBUS_B9") (pintype "unspecified"))
    )
    (net (code "81") (name "VCC_SD") (class "Default")
      (node (ref "C34") (pin "2") (pinfunction "2_2") (pintype "input"))
      (node (ref "C35") (pin "2") (pinfunction "2_2") (pintype "unspecified"))
      (node (ref "CARD3") (pin "4") (pinfunction "VDD_4") (pintype "input"))
      (node (ref "L13") (pin "2") (pinfunction "2_2") (pintype "unspecified"))
      (node (ref "R18") (pin "2") (pinfunction "2_2") (pintype "input"))
      (node (ref "R19") (pin "2") (pinfunction "2_2") (pintype "input"))
      (node (ref "R20") (pin "2") (pinfunction "2_2") (pintype "input"))
      (node (ref "R21") (pin "2") (pinfunction "2_2") (pintype "input"))
      (node (ref "R22") (pin "2") (pinfunction "2_2") (pintype "input"))
      (node (ref "R32") (pin "2") (pinfunction "2_2") (pintype "input"))
      (node (ref "TP10") (pin "1") (pinfunction "1_1") (pintype "unspecified"))
      (node (ref "TP11") (pin "1") (pinfunction "1_1") (pintype "unspecified"))
    )
    (net (code "82") (name "WE1") (class "Default")
      (node (ref "U13") (pin "4") (pinfunction "S1A_4") (pintype "unspecified"))
      (node (ref "U14") (pin "3") (pinfunction "3_3") (pintype "input"))
    )
    (net (code "83") (name "WE2") (class "Default")
      (node (ref "U13") (pin "5") (pinfunction "S2A_5") (pintype "unspecified"))
      (node (ref "U14") (pin "2") (pinfunction "2_2") (pintype "input"))
    )
    (net (code "84") (name "WE3") (class "Default")
      (node (ref "U13") (pin "6") (pinfunction "S3A_6") (pintype "unspecified"))
      (node (ref "U14") (pin "1") (pinfunction "1_1") (pintype "input"))
    )
    (net (code "85") (name "WE_MUX_0") (class "Default")
      (node (ref "SW2") (pin "13") (pinfunction "B4_13") (pintype "input"))
      (node (ref "SW2") (pin "9") (pinfunction "B8_9") (pintype "input"))
      (node (ref "TP21") (pin "1") (pinfunction "1_1") (pintype "unspecified"))
      (node (ref "U13") (pin "1") (pinfunction "A0_1") (pintype "unspecified"))
    )
    (net (code "86") (name "WE_MUX_1") (class "Default")
      (node (ref "SW2") (pin "10") (pinfunction "B7_10") (pintype "input"))
      (node (ref "SW2") (pin "14") (pinfunction "B3_14") (pintype "input"))
      (node (ref "TP22") (pin "1") (pinfunction "1_1") (pintype "unspecified"))
      (node (ref "U13") (pin "16") (pinfunction "A1_16") (pintype "unspecified"))
    )
    (net (code "87") (name "unconnected-(U1-Ain_0-Pad21)") (class "Default")
      (node (ref "U1") (pin "21") (pinfunction "Ain_0_21") (pintype "input+no_connect"))
    )
    (net (code "88") (name "unconnected-(U1-Ain_1-Pad20)") (class "Default")
      (node (ref "U1") (pin "20") (pinfunction "Ain_1_20") (pintype "input+no_connect"))
    )
    (net (code "89") (name "unconnected-(U1-Ain_2-Pad19)") (class "Default")
      (node (ref "U1") (pin "19") (pinfunction "Ain_2_19") (pintype "input+no_connect"))
    )
    (net (code "90") (name "unconnected-(U1-CE_1-Pad12)") (class "Default")
      (node (ref "U1") (pin "12") (pinfunction "CE_1_12") (pintype "input+no_connect"))
    )
    (net (code "91") (name "unconnected-(U1-GPIO_4-Pad11)") (class "Default")
      (node (ref "U1") (pin "11") (pinfunction "GPIO_4_11") (pintype "bidirectional+no_connect"))
    )
    (net (code "92") (name "unconnected-(U1-GPIO_5-Pad22)") (class "Default")
      (node (ref "U1") (pin "22") (pinfunction "GPIO_5_22") (pintype "bidirectional+no_connect"))
    )
    (net (code "93") (name "unconnected-(U1-GPIO_6-Pad23)") (class "Default")
      (node (ref "U1") (pin "23") (pinfunction "GPIO_6_23") (pintype "bidirectional+no_connect"))
    )
    (net (code "94") (name "unconnected-(U1-GPIO_7-Pad24)") (class "Default")
      (node (ref "U1") (pin "24") (pinfunction "GPIO_7_24") (pintype "bidirectional+no_connect"))
    )
    (net (code "95") (name "unconnected-(U1-I2C_SCL-Pad25)") (class "Default")
      (node (ref "U1") (pin "25") (pinfunction "I2C_SCL_25") (pintype "input+no_connect"))
    )
    (net (code "96") (name "unconnected-(U1-I2C_SDA-Pad26)") (class "Default")
      (node (ref "U1") (pin "26") (pinfunction "I2C_SDA_26") (pintype "bidirectional+no_connect"))
    )
    (net (code "97") (name "unconnected-(U1-NC-Pad1)") (class "Default")
      (node (ref "U1") (pin "1") (pinfunction "NC_1") (pintype "no_connect"))
    )
    (net (code "98") (name "unconnected-(U1-RE_1-Pad14)") (class "Default")
      (node (ref "U1") (pin "14") (pinfunction "RE_1_14") (pintype "input+no_connect"))
    )
    (net (code "99") (name "unconnected-(U1-WE_1-Pad13)") (class "Default")
      (node (ref "U1") (pin "13") (pinfunction "WE_1_13") (pintype "input+no_connect"))
    )
    (net (code "100") (name "unconnected-(U4-IO1-Pad39)") (class "Default")
      (node (ref "U4") (pin "39") (pinfunction "IO1_39") (pintype "unspecified+no_connect"))
    )
    (net (code "101") (name "unconnected-(U4-IO2-Pad38)") (class "Default")
      (node (ref "U4") (pin "38") (pinfunction "IO2_38") (pintype "unspecified+no_connect"))
    )
    (net (code "102") (name "unconnected-(U4-IO3-Pad15)") (class "Default")
      (node (ref "U4") (pin "15") (pinfunction "IO3_15") (pintype "unspecified+no_connect"))
    )
    (net (code "103") (name "unconnected-(U4-IO8-Pad12)") (class "Default")
      (node (ref "U4") (pin "12") (pinfunction "IO8_12") (pintype "unspecified+no_connect"))
    )
    (net (code "104") (name "unconnected-(U4-IO9-Pad17)") (class "Default")
      (node (ref "U4") (pin "17") (pinfunction "IO9_17") (pintype "unspecified+no_connect"))
    )
    (net (code "105") (name "unconnected-(U4-IO12-Pad20)") (class "Default")
      (node (ref "U4") (pin "20") (pinfunction "IO12_20") (pintype "unspecified+no_connect"))
    )
    (net (code "106") (name "unconnected-(U4-IO13-Pad21)") (class "Default")
      (node (ref "U4") (pin "21") (pinfunction "IO13_21") (pintype "unspecified+no_connect"))
    )
    (net (code "107") (name "unconnected-(U4-IO14-Pad22)") (class "Default")
      (node (ref "U4") (pin "22") (pinfunction "IO14_22") (pintype "unspecified+no_connect"))
    )
    (net (code "108") (name "unconnected-(U4-IO19-Pad13)") (class "Default")
      (node (ref "U4") (pin "13") (pinfunction "IO19_13") (pintype "unspecified+no_connect"))
    )
    (net (code "109") (name "unconnected-(U4-IO20-Pad14)") (class "Default")
      (node (ref "U4") (pin "14") (pinfunction "IO20_14") (pintype "unspecified+no_connect"))
    )
    (net (code "110") (name "unconnected-(U4-IO42-Pad35)") (class "Default")
      (node (ref "U4") (pin "35") (pinfunction "IO42_35") (pintype "unspecified+no_connect"))
    )
    (net (code "111") (name "unconnected-(U4-IO45-Pad26)") (class "Default")
      (node (ref "U4") (pin "26") (pinfunction "IO45_26") (pintype "unspecified+no_connect"))
    )
    (net (code "112") (name "unconnected-(U4-IO46-Pad16)") (class "Default")
      (node (ref "U4") (pin "16") (pinfunction "IO46_16") (pintype "unspecified+no_connect"))
    )
    (net (code "113") (name "unconnected-(U5-CBUS2-Pad7)") (class "Default")
      (node (ref "U5") (pin "7") (pinfunction "CBUS2_7") (pintype "bidirectional+no_connect"))
    )
    (net (code "114") (name "unconnected-(U5-CBUS3-Pad16)") (class "Default")
      (node (ref "U5") (pin "16") (pinfunction "CBUS3_16") (pintype "bidirectional+no_connect"))
    )
    (net (code "115") (name "unconnected-(U5-CTS#-Pad6)") (class "Default")
      (node (ref "U5") (pin "6") (pinfunction "CTS#_6") (pintype "unspecified+no_connect"))
    )
    (net (code "116") (name "unconnected-(U5-RTS#-Pad2)") (class "Default")
      (node (ref "U5") (pin "2") (pinfunction "RTS#_2") (pintype "output+no_connect"))
    )
    (net (code "117") (name "unconnected-(U6-CTS#-Pad9)") (class "Default")
      (node (ref "U6") (pin "9") (pinfunction "CTS#_9") (pintype "unspecified+no_connect"))
    )
    (net (code "118") (name "unconnected-(U6-DCD#-Pad12)") (class "Default")
      (node (ref "U6") (pin "12") (pinfunction "DCD#_12") (pintype "unspecified+no_connect"))
    )
    (net (code "119") (name "unconnected-(U6-DSR#-Pad10)") (class "Default")
      (node (ref "U6") (pin "10") (pinfunction "DSR#_10") (pintype "unspecified+no_connect"))
    )
    (net (code "120") (name "unconnected-(U6-NC.-Pad7)") (class "Default")
      (node (ref "U6") (pin "7") (pinfunction "NC._7") (pintype "unspecified+no_connect"))
    )
    (net (code "121") (name "unconnected-(U6-OUT#-Pad8)") (class "Default")
      (node (ref "U6") (pin "8") (pinfunction "OUT#_8") (pintype "unspecified+no_connect"))
    )
    (net (code "122") (name "unconnected-(U6-R232-Pad15)") (class "Default")
      (node (ref "U6") (pin "15") (pinfunction "R232_15") (pintype "unspecified+no_connect"))
    )
    (net (code "123") (name "unconnected-(U6-RI#-Pad11)") (class "Default")
      (node (ref "U6") (pin "11") (pinfunction "RI#_11") (pintype "unspecified+no_connect"))
    )
    (net (code "124") (name "unconnected-(U10-PG-Pad4)") (class "Default")
      (node (ref "U10") (pin "4") (pinfunction "PG_4") (pintype "unspecified+no_connect"))
    )
    (net (code "125") (name "unconnected-(U12-S4A-Pad7)") (class "Default")
      (node (ref "U12") (pin "7") (pinfunction "S4A_7") (pintype "unspecified+no_connect"))
    )
    (net (code "126") (name "unconnected-(U12-S4B-Pad10)") (class "Default")
      (node (ref "U12") (pin "10") (pinfunction "S4B_10") (pintype "unspecified+no_connect"))
    )
    (net (code "127") (name "unconnected-(U13-DB-Pad9)") (class "Default")
      (node (ref "U13") (pin "9") (pinfunction "DB_9") (pintype "unspecified+no_connect"))
    )
    (net (code "128") (name "unconnected-(U13-S1B-Pad13)") (class "Default")
      (node (ref "U13") (pin "13") (pinfunction "S1B_13") (pintype "unspecified+no_connect"))
    )
    (net (code "129") (name "unconnected-(U13-S2B-Pad12)") (class "Default")
      (node (ref "U13") (pin "12") (pinfunction "S2B_12") (pintype "unspecified+no_connect"))
    )
    (net (code "130") (name "unconnected-(U13-S3B-Pad11)") (class "Default")
      (node (ref "U13") (pin "11") (pinfunction "S3B_11") (pintype "unspecified+no_connect"))
    )
    (net (code "131") (name "unconnected-(U13-S4A-Pad7)") (class "Default")
      (node (ref "U13") (pin "7") (pinfunction "S4A_7") (pintype "unspecified+no_connect"))
    )
    (net (code "132") (name "unconnected-(U13-S4B-Pad10)") (class "Default")
      (node (ref "U13") (pin "10") (pinfunction "S4B_10") (pintype "unspecified+no_connect"))
    )
    (net (code "133") (name "unconnected-(USBC1-SBU1-PadA8)") (class "Default")
      (node (ref "USBC1") (pin "A8") (pinfunction "SBU1_A8") (pintype "unspecified+no_connect"))
    )
    (net (code "134") (name "unconnected-(USBC1-SBU2-PadB8)") (class "Default")
      (node (ref "USBC1") (pin "B8") (pinfunction "SBU2_B8") (pintype "unspecified+no_connect"))
    )
    (net (code "135") (name "unconnected-(USBC2-SBU1-PadA8)") (class "Default")
      (node (ref "USBC2") (pin "A8") (pinfunction "SBU1_A8") (pintype "unspecified+no_connect"))
    )
    (net (code "136") (name "unconnected-(USBC2-SBU2-PadB8)") (class "Default")
      (node (ref "USBC2") (pin "B8") (pinfunction "SBU2_B8") (pintype "unspecified+no_connect"))
    )
  )
)
